# video_test.net
KiCad netlist of a schematic drawn in EAGLE
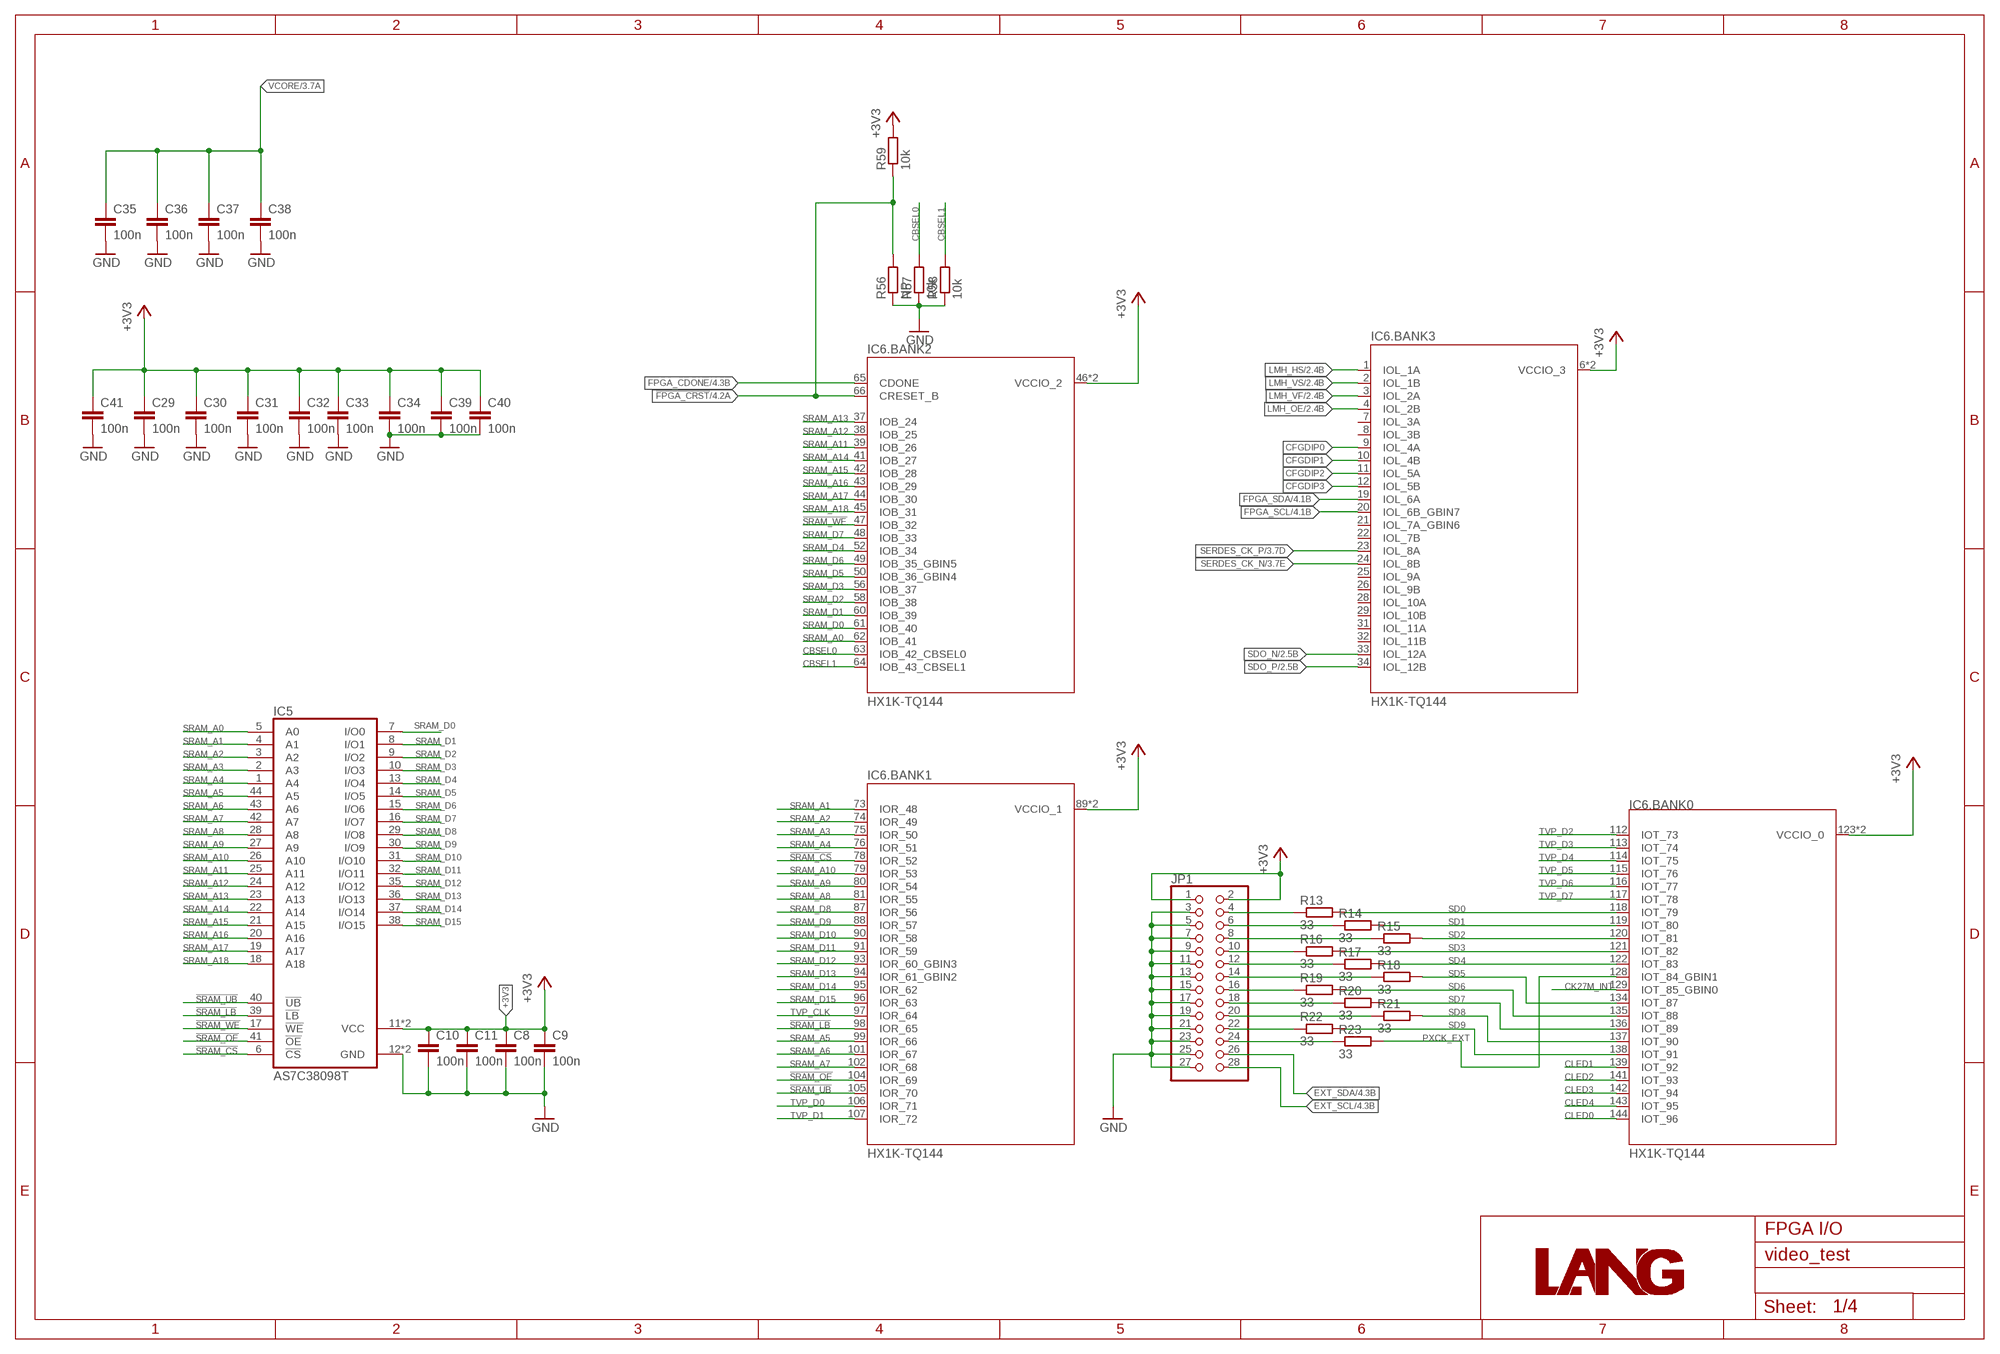
[diagram p0: schematic, sheet 1]
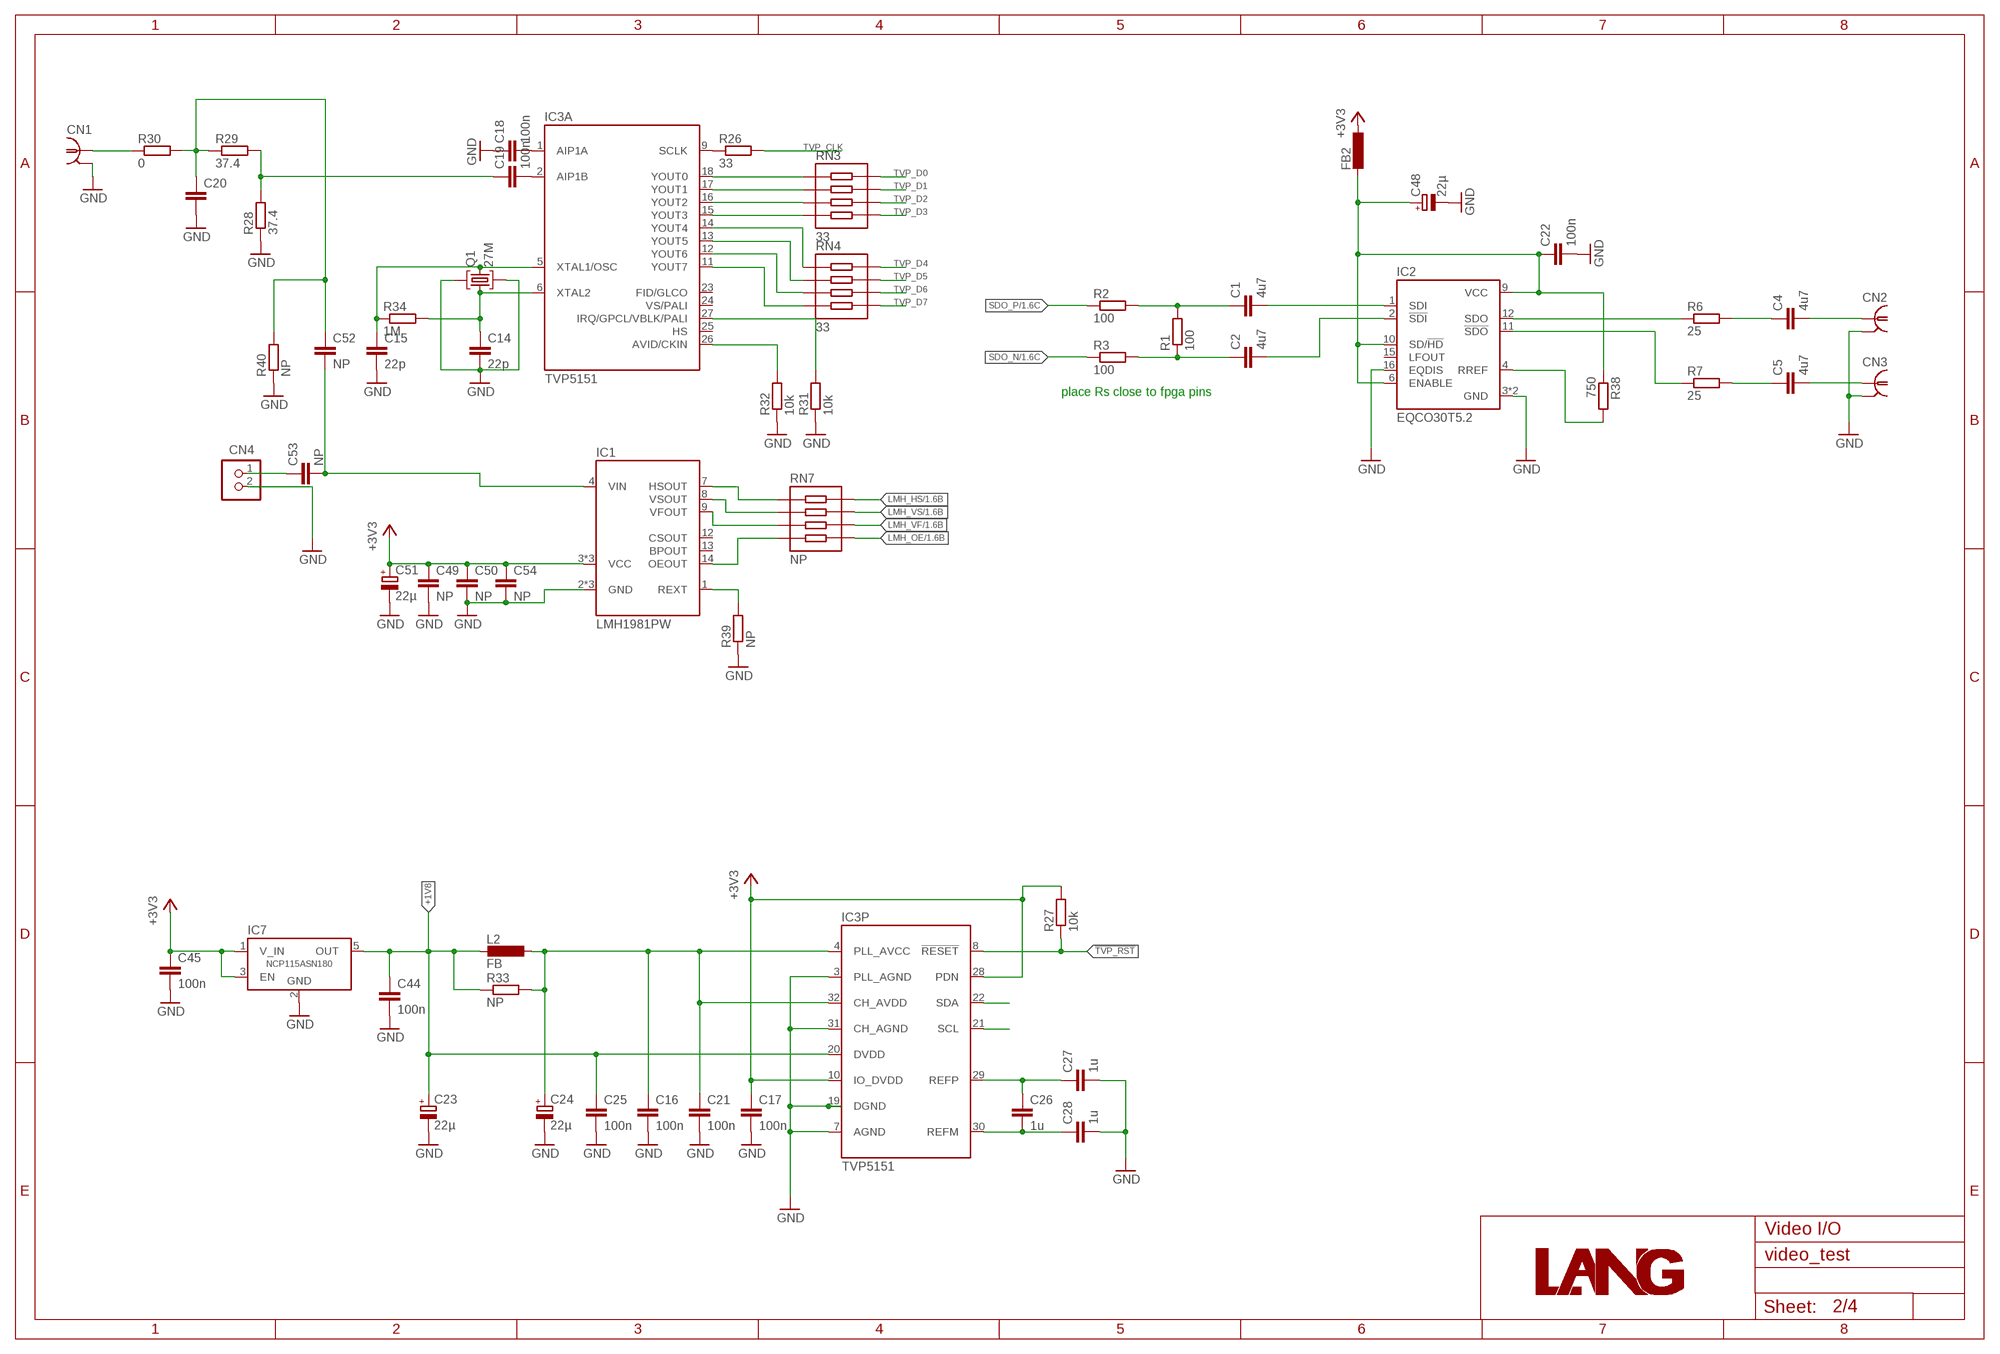
[diagram p1: schematic, sheet 2]
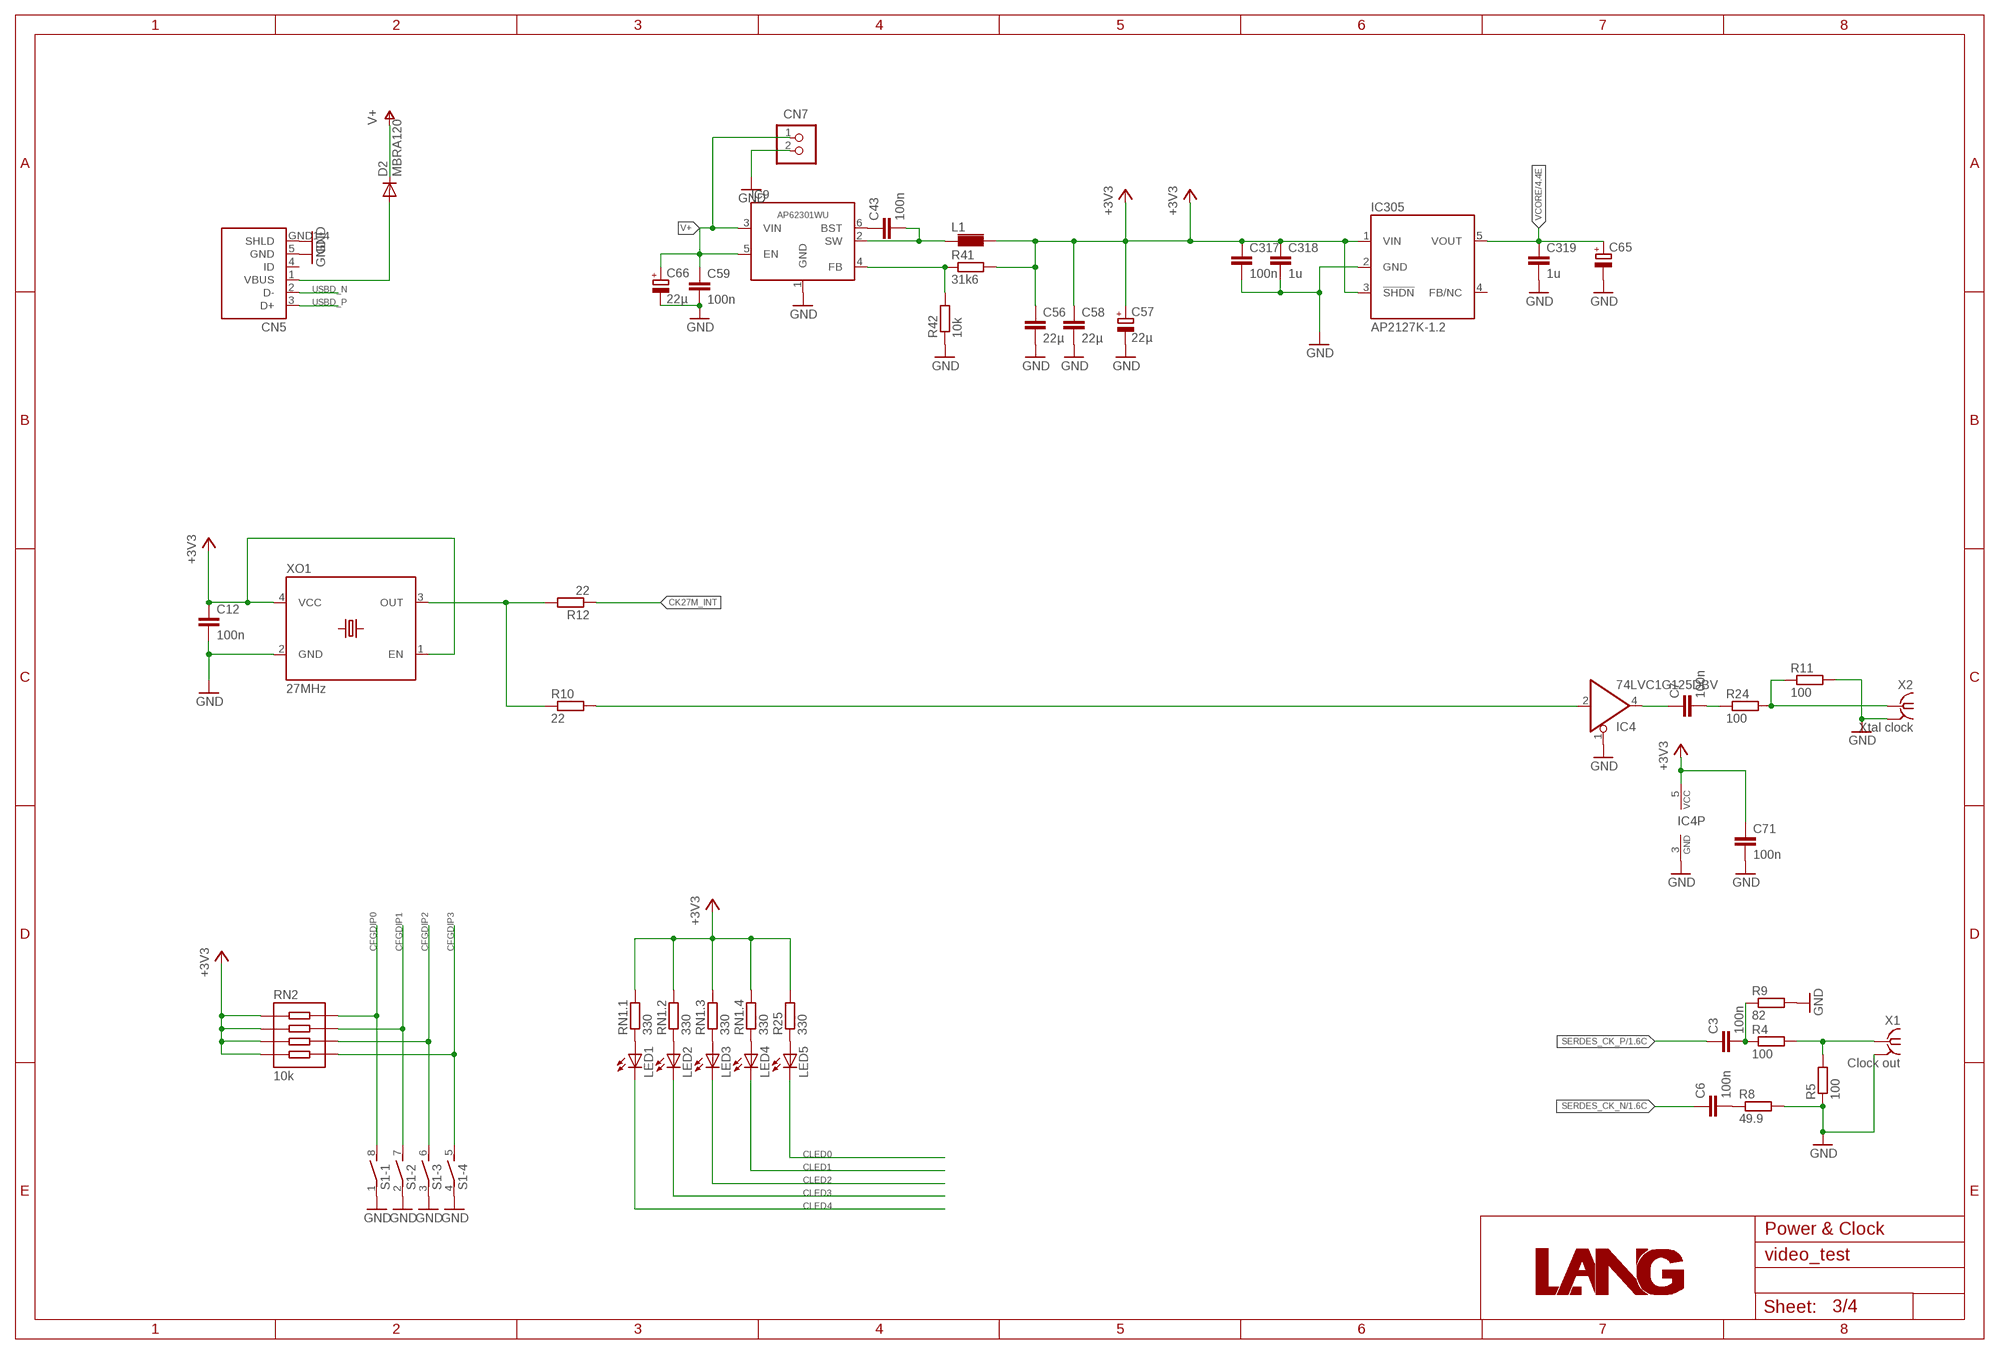
[diagram p2: schematic, sheet 3]
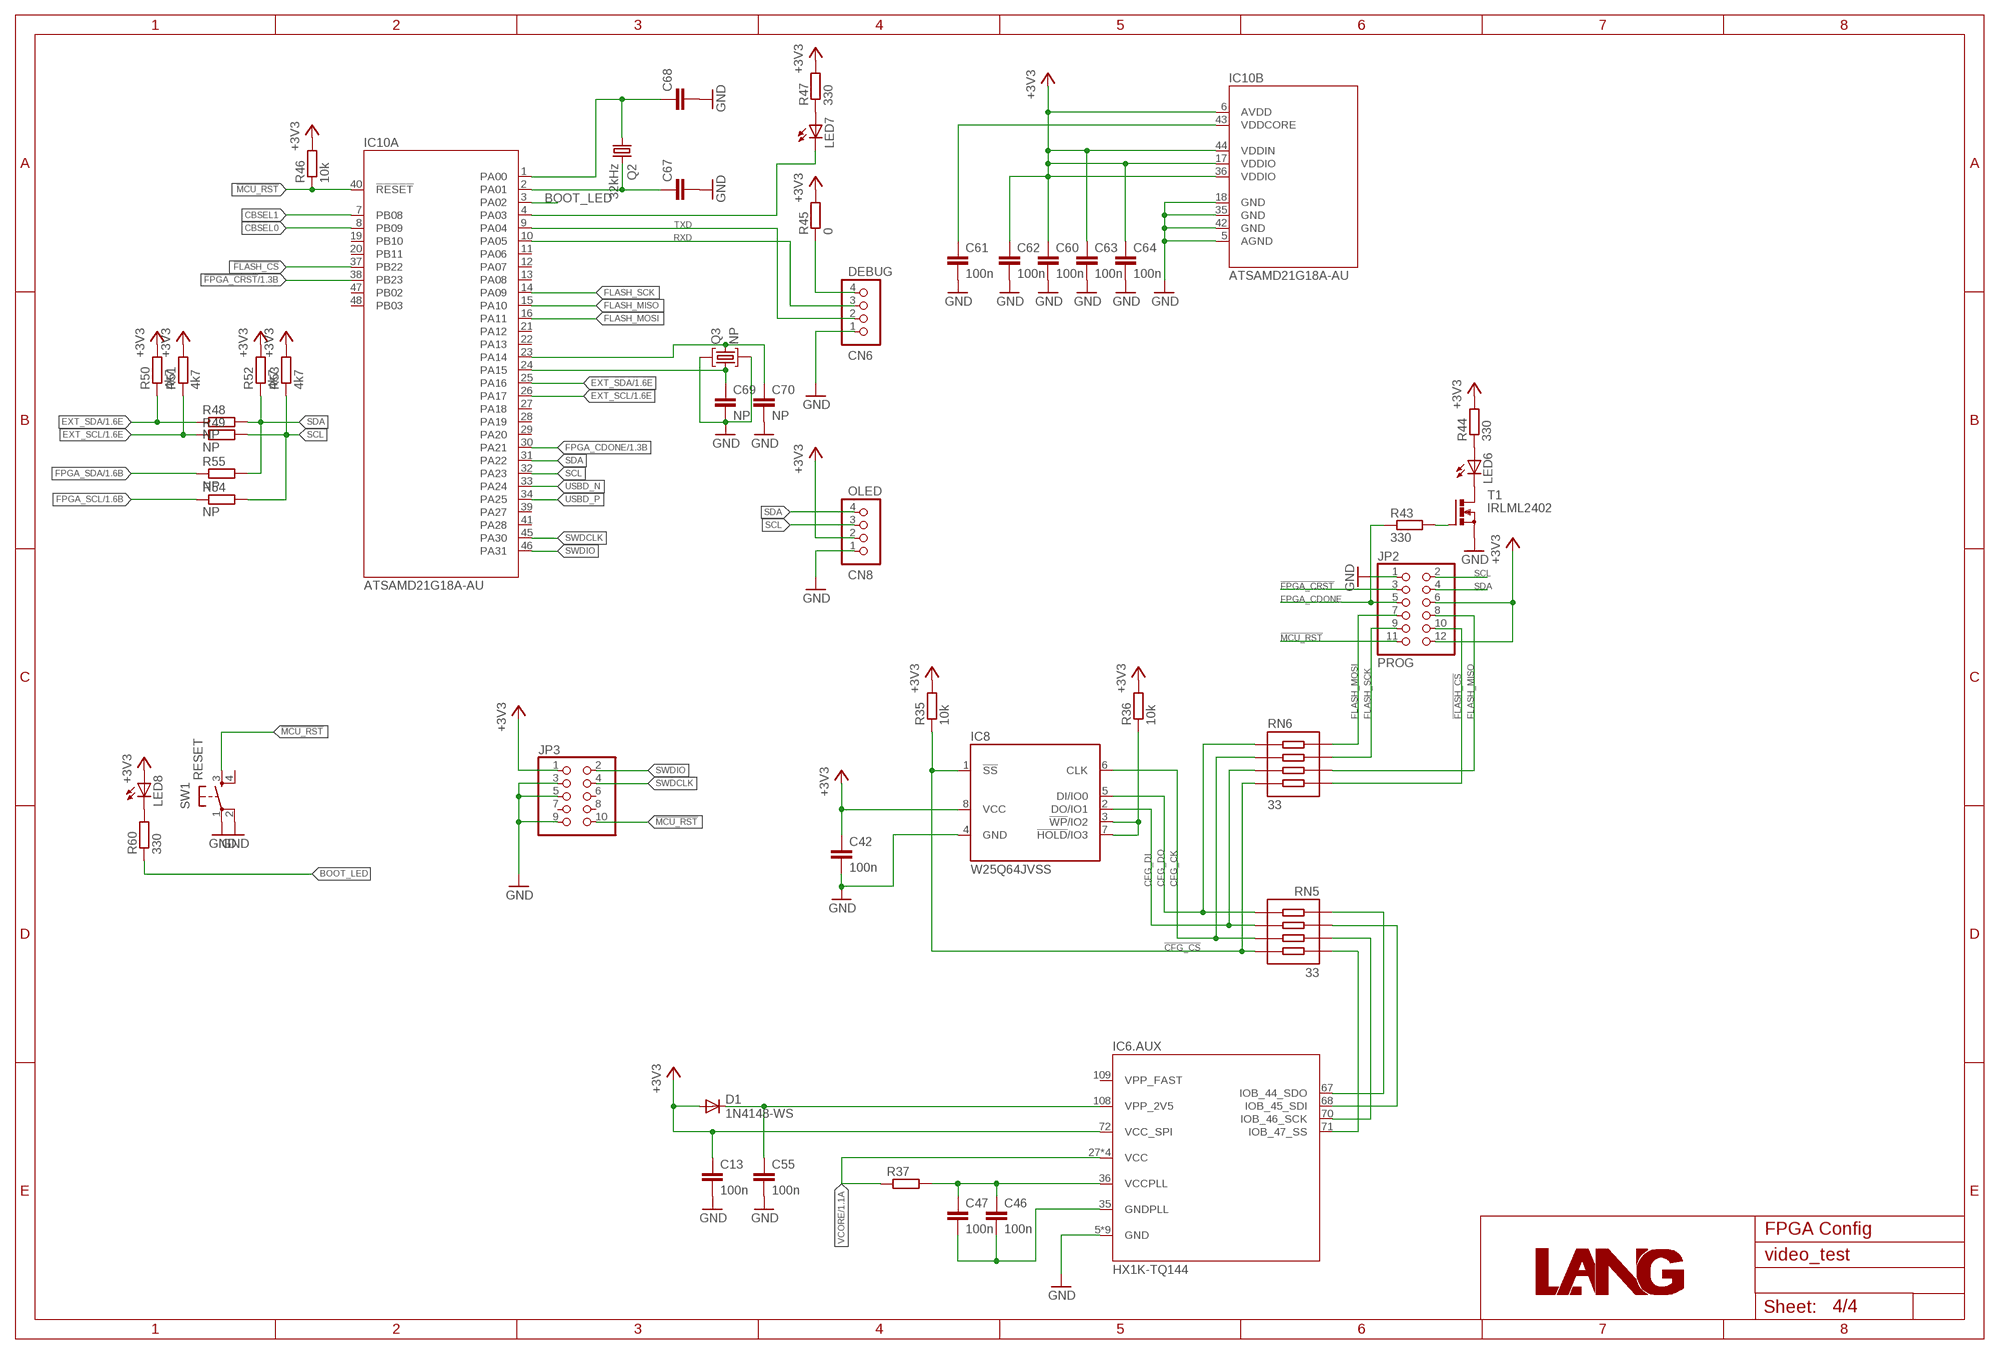
[diagram p3: schematic, sheet 4]

(export (version "E")
  (design (tool "Eeschema 10.0.6"))
  (components
    (comp (ref "C8")
      (value "100n")
      (footprint "eagle-import:C0603")
      (libsource (lib "eagle-import") (part "C-EUC0603"))
    )
    (comp (ref "C9")
      (value "100n")
      (footprint "eagle-import:C0603")
      (libsource (lib "eagle-import") (part "C-EUC0603"))
    )
    (comp (ref "C10")
      (value "100n")
      (footprint "eagle-import:C0402")
      (libsource (lib "eagle-import") (part "C-EUC0402"))
    )
    (comp (ref "C11")
      (value "100n")
      (footprint "eagle-import:C0402")
      (libsource (lib "eagle-import") (part "C-EUC0402"))
    )
    (comp (ref "C29")
      (value "100n")
      (footprint "eagle-import:C0402")
      (libsource (lib "eagle-import") (part "C-EUC0402"))
    )
    (comp (ref "C30")
      (value "100n")
      (footprint "eagle-import:C0402")
      (libsource (lib "eagle-import") (part "C-EUC0402"))
    )
    (comp (ref "C31")
      (value "100n")
      (footprint "eagle-import:C0402")
      (libsource (lib "eagle-import") (part "C-EUC0402"))
    )
    (comp (ref "C32")
      (value "100n")
      (footprint "eagle-import:C0402")
      (libsource (lib "eagle-import") (part "C-EUC0402"))
    )
    (comp (ref "C33")
      (value "100n")
      (footprint "eagle-import:C0402")
      (libsource (lib "eagle-import") (part "C-EUC0402"))
    )
    (comp (ref "C34")
      (value "100n")
      (footprint "eagle-import:C0402")
      (libsource (lib "eagle-import") (part "C-EUC0402"))
    )
    (comp (ref "C35")
      (value "100n")
      (footprint "eagle-import:C0402")
      (libsource (lib "eagle-import") (part "C-EUC0402"))
    )
    (comp (ref "C36")
      (value "100n")
      (footprint "eagle-import:C0402")
      (libsource (lib "eagle-import") (part "C-EUC0402"))
    )
    (comp (ref "C37")
      (value "100n")
      (footprint "eagle-import:C0402")
      (libsource (lib "eagle-import") (part "C-EUC0402"))
    )
    (comp (ref "C38")
      (value "100n")
      (footprint "eagle-import:C0402")
      (libsource (lib "eagle-import") (part "C-EUC0402"))
    )
    (comp (ref "C39")
      (value "100n")
      (footprint "eagle-import:C0402")
      (libsource (lib "eagle-import") (part "C-EUC0402"))
    )
    (comp (ref "C40")
      (value "100n")
      (footprint "eagle-import:C0402")
      (libsource (lib "eagle-import") (part "C-EUC0402"))
    )
    (comp (ref "C41")
      (value "100n")
      (footprint "eagle-import:C0402")
      (libsource (lib "eagle-import") (part "C-EUC0402"))
    )
    (comp (ref "IC5")
      (value "AS7C38098T")
      (footprint "eagle-import:TSOPII-Z44")
      (libsource (lib "eagle-import") (part "AS7C38098T"))
    )
    (comp (ref "IC6")
      (value "HX1K-TQ144")
      (footprint "eagle-import:QFP50P2200X2200X160-144N")
      (libsource (lib "eagle-import") (part "HX1K-TQ144"))
    )
    (comp (ref "JP1")
      (value "PINHD-2X14")
      (footprint "eagle-import:2X14")
      (libsource (lib "eagle-import") (part "PINHD-2X14"))
    )
    (comp (ref "R13")
      (value "33")
      (footprint "eagle-import:R0603")
      (libsource (lib "eagle-import") (part "R-EU_R0603"))
    )
    (comp (ref "R14")
      (value "33")
      (footprint "eagle-import:R0603")
      (libsource (lib "eagle-import") (part "R-EU_R0603"))
    )
    (comp (ref "R15")
      (value "33")
      (footprint "eagle-import:R0603")
      (libsource (lib "eagle-import") (part "R-EU_R0603"))
    )
    (comp (ref "R16")
      (value "33")
      (footprint "eagle-import:R0603")
      (libsource (lib "eagle-import") (part "R-EU_R0603"))
    )
    (comp (ref "R17")
      (value "33")
      (footprint "eagle-import:R0603")
      (libsource (lib "eagle-import") (part "R-EU_R0603"))
    )
    (comp (ref "R18")
      (value "33")
      (footprint "eagle-import:R0603")
      (libsource (lib "eagle-import") (part "R-EU_R0603"))
    )
    (comp (ref "R19")
      (value "33")
      (footprint "eagle-import:R0603")
      (libsource (lib "eagle-import") (part "R-EU_R0603"))
    )
    (comp (ref "R20")
      (value "33")
      (footprint "eagle-import:R0603")
      (libsource (lib "eagle-import") (part "R-EU_R0603"))
    )
    (comp (ref "R21")
      (value "33")
      (footprint "eagle-import:R0603")
      (libsource (lib "eagle-import") (part "R-EU_R0603"))
    )
    (comp (ref "R22")
      (value "33")
      (footprint "eagle-import:R0603")
      (libsource (lib "eagle-import") (part "R-EU_R0603"))
    )
    (comp (ref "R23")
      (value "33")
      (footprint "eagle-import:R0603")
      (libsource (lib "eagle-import") (part "R-EU_R0603"))
    )
    (comp (ref "R56")
      (value "NP")
      (footprint "eagle-import:R0402")
      (libsource (lib "eagle-import") (part "R-EU_R0402"))
    )
    (comp (ref "R57")
      (value "10k")
      (footprint "eagle-import:R0402")
      (libsource (lib "eagle-import") (part "R-EU_R0402"))
    )
    (comp (ref "R58")
      (value "10k")
      (footprint "eagle-import:R0402")
      (libsource (lib "eagle-import") (part "R-EU_R0402"))
    )
    (comp (ref "R59")
      (value "10k")
      (footprint "eagle-import:R0402")
      (libsource (lib "eagle-import") (part "R-EU_R0402"))
    )
    (comp (ref "C1")
      (value "4u7")
      (footprint "eagle-import:C0603")
      (libsource (lib "eagle-import") (part "C-EUC0603"))
    )
    (comp (ref "C2")
      (value "4u7")
      (footprint "eagle-import:C0603")
      (libsource (lib "eagle-import") (part "C-EUC0603"))
    )
    (comp (ref "C4")
      (value "4u7")
      (footprint "eagle-import:C0603")
      (libsource (lib "eagle-import") (part "C-EUC0603"))
    )
    (comp (ref "C5")
      (value "4u7")
      (footprint "eagle-import:C0603")
      (libsource (lib "eagle-import") (part "C-EUC0603"))
    )
    (comp (ref "C14")
      (value "22p")
      (footprint "eagle-import:C0603")
      (libsource (lib "eagle-import") (part "C-EUC0603"))
    )
    (comp (ref "C15")
      (value "22p")
      (footprint "eagle-import:C0603")
      (libsource (lib "eagle-import") (part "C-EUC0603"))
    )
    (comp (ref "C16")
      (value "100n")
      (footprint "eagle-import:C0402")
      (libsource (lib "eagle-import") (part "C-EUC0402"))
    )
    (comp (ref "C17")
      (value "100n")
      (footprint "eagle-import:C0402")
      (libsource (lib "eagle-import") (part "C-EUC0402"))
    )
    (comp (ref "C18")
      (value "100n")
      (footprint "eagle-import:C0402")
      (libsource (lib "eagle-import") (part "C-EUC0402"))
    )
    (comp (ref "C19")
      (value "100n")
      (footprint "eagle-import:C0402")
      (libsource (lib "eagle-import") (part "C-EUC0402"))
    )
    (comp (ref "C20")
      (value "C-EUC0603")
      (footprint "eagle-import:C0603")
      (libsource (lib "eagle-import") (part "C-EUC0603"))
    )
    (comp (ref "C21")
      (value "100n")
      (footprint "eagle-import:C0402")
      (libsource (lib "eagle-import") (part "C-EUC0402"))
    )
    (comp (ref "C22")
      (value "100n")
      (footprint "eagle-import:C0402")
      (libsource (lib "eagle-import") (part "C-EUC0402"))
    )
    (comp (ref "C23")
      (value "22µ")
      (footprint "eagle-import:B_3528-21R")
      (libsource (lib "eagle-import") (part "CPOL-EUB/3528-21R"))
    )
    (comp (ref "C24")
      (value "22µ")
      (footprint "eagle-import:B_3528-21R")
      (libsource (lib "eagle-import") (part "CPOL-EUB/3528-21R"))
    )
    (comp (ref "C25")
      (value "100n")
      (footprint "eagle-import:C0402")
      (libsource (lib "eagle-import") (part "C-EUC0402"))
    )
    (comp (ref "C26")
      (value "1u")
      (footprint "eagle-import:C0603")
      (libsource (lib "eagle-import") (part "C-EUC0603"))
    )
    (comp (ref "C27")
      (value "1u")
      (footprint "eagle-import:C0603")
      (libsource (lib "eagle-import") (part "C-EUC0603"))
    )
    (comp (ref "C28")
      (value "1u")
      (footprint "eagle-import:C0603")
      (libsource (lib "eagle-import") (part "C-EUC0603"))
    )
    (comp (ref "C44")
      (value "100n")
      (footprint "eagle-import:C0603")
      (libsource (lib "eagle-import") (part "C-EUC0603"))
    )
    (comp (ref "C45")
      (value "100n")
      (footprint "eagle-import:C0603")
      (libsource (lib "eagle-import") (part "C-EUC0603"))
    )
    (comp (ref "C48")
      (value "22µ")
      (footprint "eagle-import:PANASONIC_B")
      (libsource (lib "eagle-import") (part "CPOL-EUB"))
    )
    (comp (ref "C49")
      (value "NP")
      (footprint "eagle-import:C0402")
      (libsource (lib "eagle-import") (part "C-EUC0402"))
    )
    (comp (ref "C50")
      (value "NP")
      (footprint "eagle-import:C0402")
      (libsource (lib "eagle-import") (part "C-EUC0402"))
    )
    (comp (ref "C51")
      (value "22µ")
      (footprint "eagle-import:PANASONIC_B")
      (libsource (lib "eagle-import") (part "CPOL-EUB"))
    )
    (comp (ref "C52")
      (value "NP")
      (footprint "eagle-import:C0603")
      (libsource (lib "eagle-import") (part "C-EUC0603"))
    )
    (comp (ref "C53")
      (value "NP")
      (footprint "eagle-import:C0603")
      (libsource (lib "eagle-import") (part "C-EUC0603"))
    )
    (comp (ref "C54")
      (value "NP")
      (footprint "eagle-import:C0402")
      (libsource (lib "eagle-import") (part "C-EUC0402"))
    )
    (comp (ref "CN1")
      (value "BU-BNC-RA")
      (footprint "eagle-import:AMP_227161")
      (libsource (lib "eagle-import") (part "BU-BNC-RA"))
    )
    (comp (ref "CN2")
      (value "BU-BNC-RA")
      (footprint "eagle-import:AMP_227161")
      (libsource (lib "eagle-import") (part "BU-BNC-RA"))
    )
    (comp (ref "CN3")
      (value "BU-BNC-RA")
      (footprint "eagle-import:AMP_227161")
      (libsource (lib "eagle-import") (part "BU-BNC-RA"))
    )
    (comp (ref "CN4")
      (value "JST-XH2")
      (footprint "eagle-import:B2B-XH")
      (libsource (lib "eagle-import") (part "JST-XH2"))
    )
    (comp (ref "FB2")
      (value "L-EU_L0603")
      (footprint "eagle-import:R0603")
      (libsource (lib "eagle-import") (part "L-EU_L0603"))
    )
    (comp (ref "IC1")
      (value "LMH1981PW")
      (footprint "eagle-import:TSSOP14")
      (libsource (lib "eagle-import") (part "LMH1981PW"))
    )
    (comp (ref "IC2")
      (value "EQCO30T5.2")
      (footprint "eagle-import:QFN16_065")
      (libsource (lib "eagle-import") (part "EQCO30T5.2"))
    )
    (comp (ref "IC3")
      (value "TVP5151")
      (footprint "eagle-import:SPQFP32")
      (libsource (lib "eagle-import") (part "TVP5151"))
    )
    (comp (ref "IC7")
      (value "NCP115ASN180")
      (footprint "eagle-import:SOT23-5")
      (libsource (lib "eagle-import") (part "NCP115ASN180"))
    )
    (comp (ref "L2")
      (value "FB")
      (footprint "eagle-import:R0805")
      (libsource (lib "eagle-import") (part "L-EU_L0805"))
    )
    (comp (ref "Q1")
      (value "27M")
      (footprint "eagle-import:MT")
      (libsource (lib "eagle-import") (part "CRYSTAL_SHIELDEDMT"))
    )
    (comp (ref "R1")
      (value "100")
      (footprint "eagle-import:R0603")
      (libsource (lib "eagle-import") (part "R-EU_R0603"))
    )
    (comp (ref "R2")
      (value "100")
      (footprint "eagle-import:R0603")
      (libsource (lib "eagle-import") (part "R-EU_R0603"))
    )
    (comp (ref "R3")
      (value "100")
      (footprint "eagle-import:R0603")
      (libsource (lib "eagle-import") (part "R-EU_R0603"))
    )
    (comp (ref "R6")
      (value "25")
      (footprint "eagle-import:R0603")
      (libsource (lib "eagle-import") (part "R-EU_R0603"))
    )
    (comp (ref "R7")
      (value "25")
      (footprint "eagle-import:R0603")
      (libsource (lib "eagle-import") (part "R-EU_R0603"))
    )
    (comp (ref "R26")
      (value "33")
      (footprint "eagle-import:R0603")
      (libsource (lib "eagle-import") (part "R-EU_R0603"))
    )
    (comp (ref "R27")
      (value "10k")
      (footprint "eagle-import:R0402")
      (libsource (lib "eagle-import") (part "R-EU_R0402"))
    )
    (comp (ref "R28")
      (value "37.4")
      (footprint "eagle-import:R0603")
      (libsource (lib "eagle-import") (part "R-EU_R0603"))
    )
    (comp (ref "R29")
      (value "37.4")
      (footprint "eagle-import:R0603")
      (libsource (lib "eagle-import") (part "R-EU_R0603"))
    )
    (comp (ref "R30")
      (value "0")
      (footprint "eagle-import:R0603")
      (libsource (lib "eagle-import") (part "R-EU_R0603"))
    )
    (comp (ref "R31")
      (value "10k")
      (footprint "eagle-import:R0402")
      (libsource (lib "eagle-import") (part "R-EU_R0402"))
    )
    (comp (ref "R32")
      (value "10k")
      (footprint "eagle-import:R0402")
      (libsource (lib "eagle-import") (part "R-EU_R0402"))
    )
    (comp (ref "R33")
      (value "NP")
      (footprint "eagle-import:R0603")
      (libsource (lib "eagle-import") (part "R-EU_R0603"))
    )
    (comp (ref "R34")
      (value "1M")
      (footprint "eagle-import:R0603")
      (libsource (lib "eagle-import") (part "R-EU_R0603"))
    )
    (comp (ref "R38")
      (value "750")
      (footprint "eagle-import:R0603")
      (libsource (lib "eagle-import") (part "R-EU_R0603"))
    )
    (comp (ref "R39")
      (value "NP")
      (footprint "eagle-import:R0603")
      (libsource (lib "eagle-import") (part "R-EU_R0603"))
    )
    (comp (ref "R40")
      (value "NP")
      (footprint "eagle-import:R0603")
      (libsource (lib "eagle-import") (part "R-EU_R0603"))
    )
    (comp (ref "RN3")
      (value "33")
      (footprint "eagle-import:CTS742C083")
      (libsource (lib "eagle-import") (part "RN4-1-1206"))
    )
    (comp (ref "RN4")
      (value "33")
      (footprint "eagle-import:CTS742C083")
      (libsource (lib "eagle-import") (part "RN4-1-1206"))
    )
    (comp (ref "RN7")
      (value "NP")
      (footprint "eagle-import:CTS742C083")
      (libsource (lib "eagle-import") (part "RN4-1-1206"))
    )
    (comp (ref "C13")
      (value "100n")
      (footprint "eagle-import:C0402")
      (libsource (lib "eagle-import") (part "C-EUC0402"))
    )
    (comp (ref "C42")
      (value "100n")
      (footprint "eagle-import:C0603")
      (libsource (lib "eagle-import") (part "C-EUC0603"))
    )
    (comp (ref "C46")
      (value "100n")
      (footprint "eagle-import:C0402")
      (libsource (lib "eagle-import") (part "C-EUC0402"))
    )
    (comp (ref "C47")
      (value "100n")
      (footprint "eagle-import:C0603")
      (libsource (lib "eagle-import") (part "C-EUC0603"))
    )
    (comp (ref "C55")
      (value "100n")
      (footprint "eagle-import:C0402")
      (libsource (lib "eagle-import") (part "C-EUC0402"))
    )
    (comp (ref "C60")
      (value "100n")
      (footprint "eagle-import:C0402")
      (libsource (lib "eagle-import") (part "C-EUC0402"))
    )
    (comp (ref "C61")
      (value "100n")
      (footprint "eagle-import:C0402")
      (libsource (lib "eagle-import") (part "C-EUC0402"))
    )
    (comp (ref "C62")
      (value "100n")
      (footprint "eagle-import:C0402")
      (libsource (lib "eagle-import") (part "C-EUC0402"))
    )
    (comp (ref "C63")
      (value "100n")
      (footprint "eagle-import:C0402")
      (libsource (lib "eagle-import") (part "C-EUC0402"))
    )
    (comp (ref "C64")
      (value "100n")
      (footprint "eagle-import:C0402")
      (libsource (lib "eagle-import") (part "C-EUC0402"))
    )
    (comp (ref "C67")
      (value "C-EUC0402")
      (footprint "eagle-import:C0402")
      (libsource (lib "eagle-import") (part "C-EUC0402"))
    )
    (comp (ref "C68")
      (value "C-EUC0402")
      (footprint "eagle-import:C0402")
      (libsource (lib "eagle-import") (part "C-EUC0402"))
    )
    (comp (ref "C69")
      (value "NP")
      (footprint "eagle-import:C0603")
      (libsource (lib "eagle-import") (part "C-EUC0603"))
    )
    (comp (ref "C70")
      (value "NP")
      (footprint "eagle-import:C0603")
      (libsource (lib "eagle-import") (part "C-EUC0603"))
    )
    (comp (ref "CN6")
      (value "DEBUG")
      (footprint "eagle-import:SL-254-RH-4")
      (libsource (lib "eagle-import") (part "PINHD-1X4-RH"))
    )
    (comp (ref "CN8")
      (value "OLED")
      (footprint "eagle-import:SL-254-RH-4")
      (libsource (lib "eagle-import") (part "PINHD-1X4-RH"))
    )
    (comp (ref "D1")
      (value "1N4148-WS")
      (footprint "eagle-import:SOD323")
      (libsource (lib "eagle-import") (part "1N4148-WS"))
    )
    (comp (ref "IC8")
      (value "W25Q64JVSS")
      (footprint "eagle-import:SO-08M")
      (libsource (lib "eagle-import") (part "W25QJVSS64"))
    )
    (comp (ref "IC10")
      (value "ATSAMD21G18A-AU")
      (footprint "eagle-import:TQFP48_7X7MC_MCH")
      (fields (field (name "COPYRIGHT") "Copyright (C) 2018 Accelerated Designs. All rights reserved"))
      (libsource (lib "eagle-import") (part "ATSAMD21G18A-AU"))
    )
    (comp (ref "JP2")
      (value "PROG")
      (footprint "eagle-import:2X06")
      (libsource (lib "eagle-import") (part "PINHD-2X6"))
    )
    (comp (ref "JP3")
      (value "PINHD-2X5-127")
      (footprint "eagle-import:SL127-2X5")
      (libsource (lib "eagle-import") (part "PINHD-2X5-127"))
    )
    (comp (ref "LED6")
      (value "LEDCHIP-LED0603")
      (footprint "eagle-import:CHIP-LED0603")
      (libsource (lib "eagle-import") (part "LEDCHIP-LED0603"))
    )
    (comp (ref "LED7")
      (value "LEDCHIP-LED0603")
      (footprint "eagle-import:CHIP-LED0603")
      (libsource (lib "eagle-import") (part "LEDCHIP-LED0603"))
    )
    (comp (ref "LED8")
      (value "LEDCHIP-LED0603")
      (footprint "eagle-import:CHIP-LED0603")
      (libsource (lib "eagle-import") (part "LEDCHIP-LED0603"))
    )
    (comp (ref "Q2")
      (value "32kHz")
      (footprint "eagle-import:IQXC-25")
      (libsource (lib "eagle-import") (part "CRYSTAL-IQXC-25"))
    )
    (comp (ref "Q3")
      (value "NP")
      (footprint "eagle-import:MT")
      (libsource (lib "eagle-import") (part "CRYSTAL_SHIELDEDMT"))
    )
    (comp (ref "R35")
      (value "10k")
      (footprint "eagle-import:R0603")
      (libsource (lib "eagle-import") (part "R-EU_R0603"))
    )
    (comp (ref "R36")
      (value "10k")
      (footprint "eagle-import:R0603")
      (libsource (lib "eagle-import") (part "R-EU_R0603"))
    )
    (comp (ref "R37")
      (value "R-EU_R0603")
      (footprint "eagle-import:R0603")
      (libsource (lib "eagle-import") (part "R-EU_R0603"))
    )
    (comp (ref "R43")
      (value "330")
      (footprint "eagle-import:R0603")
      (libsource (lib "eagle-import") (part "R-EU_R0603"))
    )
    (comp (ref "R44")
      (value "330")
      (footprint "eagle-import:R0603")
      (libsource (lib "eagle-import") (part "R-EU_R0603"))
    )
    (comp (ref "R45")
      (value "0")
      (footprint "eagle-import:R0603")
      (libsource (lib "eagle-import") (part "R-EU_R0603"))
    )
    (comp (ref "R46")
      (value "10k")
      (footprint "eagle-import:R0603")
      (libsource (lib "eagle-import") (part "R-EU_R0603"))
    )
    (comp (ref "R47")
      (value "330")
      (footprint "eagle-import:R0603")
      (libsource (lib "eagle-import") (part "R-EU_R0603"))
    )
    (comp (ref "R48")
      (value "NP")
      (footprint "eagle-import:R0603")
      (libsource (lib "eagle-import") (part "R-EU_R0603"))
    )
    (comp (ref "R49")
      (value "NP")
      (footprint "eagle-import:R0603")
      (libsource (lib "eagle-import") (part "R-EU_R0603"))
    )
    (comp (ref "R50")
      (value "4k7")
      (footprint "eagle-import:R0603")
      (libsource (lib "eagle-import") (part "R-EU_R0603"))
    )
    (comp (ref "R51")
      (value "4k7")
      (footprint "eagle-import:R0603")
      (libsource (lib "eagle-import") (part "R-EU_R0603"))
    )
    (comp (ref "R52")
      (value "4k7")
      (footprint "eagle-import:R0603")
      (libsource (lib "eagle-import") (part "R-EU_R0603"))
    )
    (comp (ref "R53")
      (value "4k7")
      (footprint "eagle-import:R0603")
      (libsource (lib "eagle-import") (part "R-EU_R0603"))
    )
    (comp (ref "R54")
      (value "NP")
      (footprint "eagle-import:R0402")
      (libsource (lib "eagle-import") (part "R-EU_R0402"))
    )
    (comp (ref "R55")
      (value "NP")
      (footprint "eagle-import:R0402")
      (libsource (lib "eagle-import") (part "R-EU_R0402"))
    )
    (comp (ref "R60")
      (value "330")
      (footprint "eagle-import:R0603")
      (libsource (lib "eagle-import") (part "R-EU_R0603"))
    )
    (comp (ref "RN5")
      (value "33")
      (footprint "eagle-import:CTS742C083")
      (libsource (lib "eagle-import") (part "RN4-1-1206"))
    )
    (comp (ref "RN6")
      (value "33")
      (footprint "eagle-import:CTS742C083")
      (libsource (lib "eagle-import") (part "RN4-1-1206"))
    )
    (comp (ref "SW1")
      (value "RESET")
      (footprint "eagle-import:PTS526")
      (libsource (lib "eagle-import") (part "PTS526-S15M"))
    )
    (comp (ref "T1")
      (value "IRLML2402")
      (footprint "eagle-import:SOT23")
      (libsource (lib "eagle-import") (part "IRLML2402"))
    )
    (comp (ref "C3")
      (value "100n")
      (footprint "eagle-import:C0603")
      (libsource (lib "eagle-import") (part "C-EUC0603"))
    )
    (comp (ref "C6")
      (value "100n")
      (footprint "eagle-import:C0603")
      (libsource (lib "eagle-import") (part "C-EUC0603"))
    )
    (comp (ref "C7")
      (value "100n")
      (footprint "eagle-import:C0603")
      (libsource (lib "eagle-import") (part "C-EUC0603"))
    )
    (comp (ref "C12")
      (value "100n")
      (footprint "eagle-import:C0603")
      (libsource (lib "eagle-import") (part "C-EUC0603"))
    )
    (comp (ref "C43")
      (value "100n")
      (footprint "eagle-import:C0603")
      (libsource (lib "eagle-import") (part "C-EUC0603"))
    )
    (comp (ref "C56")
      (value "22µ")
      (footprint "eagle-import:C0805")
      (libsource (lib "eagle-import") (part "C-EUC0805"))
    )
    (comp (ref "C57")
      (value "22µ")
      (footprint "eagle-import:PANASONIC_B")
      (libsource (lib "eagle-import") (part "CPOL-EUB"))
    )
    (comp (ref "C58")
      (value "22µ")
      (footprint "eagle-import:C0805")
      (libsource (lib "eagle-import") (part "C-EUC0805"))
    )
    (comp (ref "C59")
      (value "100n")
      (footprint "eagle-import:C0603")
      (libsource (lib "eagle-import") (part "C-EUC0603"))
    )
    (comp (ref "C65")
      (value "CPOL-EUB/3528-21R")
      (footprint "eagle-import:B_3528-21R")
      (libsource (lib "eagle-import") (part "CPOL-EUB/3528-21R"))
    )
    (comp (ref "C66")
      (value "22µ")
      (footprint "eagle-import:PANASONIC_C")
      (libsource (lib "eagle-import") (part "CPOL-EUC"))
    )
    (comp (ref "C71")
      (value "100n")
      (footprint "eagle-import:C0603")
      (libsource (lib "eagle-import") (part "C-EUC0603"))
    )
    (comp (ref "C317")
      (value "100n")
      (footprint "eagle-import:C0603")
      (libsource (lib "eagle-import") (part "C-EUC0603"))
    )
    (comp (ref "C318")
      (value "1u")
      (footprint "eagle-import:C0603")
      (libsource (lib "eagle-import") (part "C-EUC0603"))
    )
    (comp (ref "C319")
      (value "1u")
      (footprint "eagle-import:C0603")
      (libsource (lib "eagle-import") (part "C-EUC0603"))
    )
    (comp (ref "CN5")
      (value "USB-UJ2-MIBH-G")
      (footprint "eagle-import:UJ2-MIBH-G-SMT")
      (libsource (lib "eagle-import") (part "USB-UJ2-MIBH-G"))
    )
    (comp (ref "CN7")
      (value "JST-XH2")
      (footprint "eagle-import:B2B-XH")
      (libsource (lib "eagle-import") (part "JST-XH2"))
    )
    (comp (ref "D2")
      (value "MBRA120")
      (footprint "eagle-import:SMA")
      (libsource (lib "eagle-import") (part "MBRA120"))
    )
    (comp (ref "IC4")
      (value "74LVC1G125DBV")
      (footprint "eagle-import:SOT23-5")
      (libsource (lib "eagle-import") (part "741G125DBVLVC"))
    )
    (comp (ref "IC9")
      (value "AP62301WU")
      (footprint "eagle-import:SOT23-6L")
      (libsource (lib "eagle-import") (part "AP62301WU"))
    )
    (comp (ref "IC305")
      (value "AP2127K-1.2")
      (footprint "eagle-import:SOT23-5")
      (libsource (lib "eagle-import") (part "AP2127K-1.2"))
    )
    (comp (ref "L1")
      (value "L-TYA4020")
      (footprint "eagle-import:TYA4020")
      (libsource (lib "eagle-import") (part "L-TYA4020"))
    )
    (comp (ref "LED1")
      (value "LEDCHIP-LED0603")
      (footprint "eagle-import:CHIP-LED0603")
      (libsource (lib "eagle-import") (part "LEDCHIP-LED0603"))
    )
    (comp (ref "LED2")
      (value "LEDCHIP-LED0603")
      (footprint "eagle-import:CHIP-LED0603")
      (libsource (lib "eagle-import") (part "LEDCHIP-LED0603"))
    )
    (comp (ref "LED3")
      (value "LEDCHIP-LED0603")
      (footprint "eagle-import:CHIP-LED0603")
      (libsource (lib "eagle-import") (part "LEDCHIP-LED0603"))
    )
    (comp (ref "LED4")
      (value "LEDCHIP-LED0603")
      (footprint "eagle-import:CHIP-LED0603")
      (libsource (lib "eagle-import") (part "LEDCHIP-LED0603"))
    )
    (comp (ref "LED5")
      (value "LEDCHIP-LED0603")
      (footprint "eagle-import:CHIP-LED0603")
      (libsource (lib "eagle-import") (part "LEDCHIP-LED0603"))
    )
    (comp (ref "R4")
      (value "100")
      (footprint "eagle-import:R0603")
      (libsource (lib "eagle-import") (part "R-EU_R0603"))
    )
    (comp (ref "R5")
      (value "100")
      (footprint "eagle-import:R0603")
      (libsource (lib "eagle-import") (part "R-EU_R0603"))
    )
    (comp (ref "R8")
      (value "49.9")
      (footprint "eagle-import:R0603")
      (libsource (lib "eagle-import") (part "R-EU_R0603"))
    )
    (comp (ref "R9")
      (value "82")
      (footprint "eagle-import:R0603")
      (libsource (lib "eagle-import") (part "R-EU_R0603"))
    )
    (comp (ref "R10")
      (value "22")
      (footprint "eagle-import:R0603")
      (libsource (lib "eagle-import") (part "R-EU_R0603"))
    )
    (comp (ref "R11")
      (value "100")
      (footprint "eagle-import:R0603")
      (libsource (lib "eagle-import") (part "R-EU_R0603"))
    )
    (comp (ref "R12")
      (value "22")
      (footprint "eagle-import:R0603")
      (libsource (lib "eagle-import") (part "R-EU_R0603"))
    )
    (comp (ref "R24")
      (value "100")
      (footprint "eagle-import:R0603")
      (libsource (lib "eagle-import") (part "R-EU_R0603"))
    )
    (comp (ref "R25")
      (value "330")
      (footprint "eagle-import:R0603")
      (libsource (lib "eagle-import") (part "R-EU_R0603"))
    )
    (comp (ref "R41")
      (value "31k6")
      (footprint "eagle-import:R0603")
      (libsource (lib "eagle-import") (part "R-EU_R0603"))
    )
    (comp (ref "R42")
      (value "10k")
      (footprint "eagle-import:R0603")
      (libsource (lib "eagle-import") (part "R-EU_R0603"))
    )
    (comp (ref "RN1")
      (value "330")
      (footprint "eagle-import:CTS742C083")
      (libsource (lib "eagle-import") (part "RN4-1206"))
    )
    (comp (ref "RN2")
      (value "10k")
      (footprint "eagle-import:CTS742C083")
      (libsource (lib "eagle-import") (part "RN4-1-1206"))
    )
    (comp (ref "S1")
      (value "DIP04S")
      (footprint "eagle-import:DIP04S")
      (libsource (lib "eagle-import") (part "DIP04S"))
    )
    (comp (ref "X1")
      (value "Clock out")
      (footprint "eagle-import:BU-SMA-V")
      (libsource (lib "eagle-import") (part "BU-SMA-V"))
    )
    (comp (ref "X2")
      (value "Xtal clock")
      (footprint "eagle-import:BU-SMA-V")
      (libsource (lib "eagle-import") (part "BU-SMA-V"))
    )
    (comp (ref "XO1")
      (value "27MHz")
      (footprint "eagle-import:ECS-2333")
      (libsource (lib "eagle-import") (part "XO-SMD"))
    )
  )
  (nets
    (net (code "1") (name "+1V8") (class "Default")
      (node (ref "C23") (pin "+") (pinfunction "+_+") (pintype "passive"))
      (node (ref "C25") (pin "1") (pinfunction "1_1") (pintype "passive"))
      (node (ref "C44") (pin "1") (pinfunction "1_1") (pintype "passive"))
      (node (ref "IC3") (pin "20") (pinfunction "DVDD_20") (pintype "power_in"))
      (node (ref "IC7") (pin "5") (pinfunction "OUT_5") (pintype "output"))
      (node (ref "L2") (pin "2") (pinfunction "2_2") (pintype "passive"))
      (node (ref "R33") (pin "1") (pinfunction "1_1") (pintype "passive"))
    )
    (net (code "2") (name "+3V3") (class "Default")
      (node (ref "C10") (pin "1") (pinfunction "1_1") (pintype "passive"))
      (node (ref "C11") (pin "1") (pinfunction "1_1") (pintype "passive"))
      (node (ref "C12") (pin "1") (pinfunction "1_1") (pintype "passive"))
      (node (ref "C13") (pin "1") (pinfunction "1_1") (pintype "passive"))
      (node (ref "C17") (pin "1") (pinfunction "1_1") (pintype "passive"))
      (node (ref "C29") (pin "1") (pinfunction "1_1") (pintype "passive"))
      (node (ref "C30") (pin "1") (pinfunction "1_1") (pintype "passive"))
      (node (ref "C31") (pin "1") (pinfunction "1_1") (pintype "passive"))
      (node (ref "C317") (pin "1") (pinfunction "1_1") (pintype "passive"))
      (node (ref "C318") (pin "1") (pinfunction "1_1") (pintype "passive"))
      (node (ref "C32") (pin "1") (pinfunction "1_1") (pintype "passive"))
      (node (ref "C33") (pin "1") (pinfunction "1_1") (pintype "passive"))
      (node (ref "C34") (pin "1") (pinfunction "1_1") (pintype "passive"))
      (node (ref "C39") (pin "1") (pinfunction "1_1") (pintype "passive"))
      (node (ref "C40") (pin "1") (pinfunction "1_1") (pintype "passive"))
      (node (ref "C41") (pin "1") (pinfunction "1_1") (pintype "passive"))
      (node (ref "C42") (pin "1") (pinfunction "1_1") (pintype "passive"))
      (node (ref "C45") (pin "1") (pinfunction "1_1") (pintype "passive"))
      (node (ref "C49") (pin "1") (pinfunction "1_1") (pintype "passive"))
      (node (ref "C50") (pin "1") (pinfunction "1_1") (pintype "passive"))
      (node (ref "C51") (pin "+") (pinfunction "+_+") (pintype "passive"))
      (node (ref "C54") (pin "1") (pinfunction "1_1") (pintype "passive"))
      (node (ref "C56") (pin "1") (pinfunction "1_1") (pintype "passive"))
      (node (ref "C57") (pin "+") (pinfunction "+_+") (pintype "passive"))
      (node (ref "C58") (pin "1") (pinfunction "1_1") (pintype "passive"))
      (node (ref "C60") (pin "1") (pinfunction "1_1") (pintype "passive"))
      (node (ref "C62") (pin "1") (pinfunction "1_1") (pintype "passive"))
      (node (ref "C63") (pin "1") (pinfunction "1_1") (pintype "passive"))
      (node (ref "C64") (pin "1") (pinfunction "1_1") (pintype "passive"))
      (node (ref "C71") (pin "1") (pinfunction "1_1") (pintype "passive"))
      (node (ref "C8") (pin "1") (pinfunction "1_1") (pintype "passive"))
      (node (ref "C9") (pin "1") (pinfunction "1_1") (pintype "passive"))
      (node (ref "CN8") (pin "2") (pinfunction "2_2") (pintype "bidirectional"))
      (node (ref "D1") (pin "A") (pinfunction "A_A") (pintype "passive"))
      (node (ref "FB2") (pin "1") (pinfunction "1_1") (pintype "passive"))
      (node (ref "IC1") (pin "11") (pinfunction "VCC_11") (pintype "power_in"))
      (node (ref "IC1") (pin "3") (pinfunction "VCC_3") (pintype "power_in"))
      (node (ref "IC1") (pin "6") (pinfunction "VCC_6") (pintype "power_in"))
      (node (ref "IC10") (pin "17") (pinfunction "VDDIO_17") (pintype "power_in"))
      (node (ref "IC10") (pin "36") (pinfunction "VDDIO_36") (pintype "power_in"))
      (node (ref "IC10") (pin "44") (pinfunction "VDDIN_44") (pintype "power_in"))
      (node (ref "IC10") (pin "6") (pinfunction "AVDD_6") (pintype "power_in"))
      (node (ref "IC3") (pin "10") (pinfunction "IO_DVDD_10") (pintype "power_in"))
      (node (ref "IC3") (pin "28") (pinfunction "PDN_28") (pintype "output"))
      (node (ref "IC305") (pin "1") (pinfunction "VIN_1") (pintype "power_in"))
      (node (ref "IC305") (pin "3") (pinfunction "~{SHDN}_3") (pintype "passive"))
      (node (ref "IC4") (pin "5") (pinfunction "VCC_5") (pintype "power_in"))
      (node (ref "IC5") (pin "11") (pinfunction "VCC_11") (pintype "power_in"))
      (node (ref "IC5") (pin "33") (pinfunction "VCC_33") (pintype "power_in"))
      (node (ref "IC6") (pin "100") (pinfunction "VCCIO_1_100") (pintype "bidirectional"))
      (node (ref "IC6") (pin "123") (pinfunction "VCCIO_0_123") (pintype "bidirectional"))
      (node (ref "IC6") (pin "133") (pinfunction "VCCIO_0_133") (pintype "bidirectional"))
      (node (ref "IC6") (pin "30") (pinfunction "VCCIO_3_30") (pintype "bidirectional"))
      (node (ref "IC6") (pin "46") (pinfunction "VCCIO_2_46") (pintype "bidirectional"))
      (node (ref "IC6") (pin "57") (pinfunction "VCCIO_2_57") (pintype "bidirectional"))
      (node (ref "IC6") (pin "6") (pinfunction "VCCIO_3_6") (pintype "bidirectional"))
      (node (ref "IC6") (pin "72") (pinfunction "VCC_SPI_72") (pintype "power_in"))
      (node (ref "IC6") (pin "89") (pinfunction "VCCIO_1_89") (pintype "bidirectional"))
      (node (ref "IC7") (pin "1") (pinfunction "V_IN_1") (pintype "power_in"))
      (node (ref "IC7") (pin "3") (pinfunction "EN_3") (pintype "input"))
      (node (ref "IC8") (pin "8") (pinfunction "VCC_8") (pintype "bidirectional"))
      (node (ref "JP1") (pin "1") (pinfunction "1_1") (pintype "passive"))
      (node (ref "JP1") (pin "2") (pinfunction "2_2") (pintype "passive"))
      (node (ref "JP2") (pin "12") (pinfunction "12_12") (pintype "passive"))
      (node (ref "JP2") (pin "6") (pinfunction "6_6") (pintype "passive"))
      (node (ref "JP3") (pin "1") (pinfunction "1_1") (pintype "passive"))
      (node (ref "L1") (pin "2") (pinfunction "P$2_2") (pintype "passive"))
      (node (ref "LED8") (pin "A") (pinfunction "A_A") (pintype "passive"))
      (node (ref "R25") (pin "2") (pinfunction "2_2") (pintype "passive"))
      (node (ref "R27") (pin "2") (pinfunction "2_2") (pintype "passive"))
      (node (ref "R35") (pin "2") (pinfunction "2_2") (pintype "passive"))
      (node (ref "R36") (pin "2") (pinfunction "2_2") (pintype "passive"))
      (node (ref "R41") (pin "2") (pinfunction "2_2") (pintype "passive"))
      (node (ref "R44") (pin "2") (pinfunction "2_2") (pintype "passive"))
      (node (ref "R45") (pin "2") (pinfunction "2_2") (pintype "passive"))
      (node (ref "R46") (pin "2") (pinfunction "2_2") (pintype "passive"))
      (node (ref "R47") (pin "2") (pinfunction "2_2") (pintype "passive"))
      (node (ref "R50") (pin "2") (pinfunction "2_2") (pintype "passive"))
      (node (ref "R51") (pin "2") (pinfunction "2_2") (pintype "passive"))
      (node (ref "R52") (pin "2") (pinfunction "2_2") (pintype "passive"))
      (node (ref "R53") (pin "2") (pinfunction "2_2") (pintype "passive"))
      (node (ref "R59") (pin "2") (pinfunction "2_2") (pintype "passive"))
      (node (ref "RN1") (pin "5") (pinfunction "2_5") (pintype "passive"))
      (node (ref "RN1") (pin "6") (pinfunction "2_6") (pintype "passive"))
      (node (ref "RN1") (pin "7") (pinfunction "2_7") (pintype "passive"))
      (node (ref "RN1") (pin "8") (pinfunction "2_8") (pintype "passive"))
      (node (ref "RN2") (pin "1") (pinfunction "A1_1") (pintype "passive"))
      (node (ref "RN2") (pin "2") (pinfunction "A2_2") (pintype "passive"))
      (node (ref "RN2") (pin "3") (pinfunction "A3_3") (pintype "passive"))
      (node (ref "RN2") (pin "4") (pinfunction "A4_4") (pintype "passive"))
      (node (ref "XO1") (pin "1") (pinfunction "EN_1") (pintype "input"))
      (node (ref "XO1") (pin "4") (pinfunction "VCC_4") (pintype "power_in"))
    )
    (net (code "3") (name "BOOT_LED") (class "Default")
      (node (ref "IC10") (pin "3") (pinfunction "PA02_3") (pintype "bidirectional"))
      (node (ref "R60") (pin "1") (pinfunction "1_1") (pintype "passive"))
    )
    (net (code "4") (name "CBSEL0") (class "Default")
      (node (ref "IC10") (pin "8") (pinfunction "PB09_8") (pintype "bidirectional"))
      (node (ref "IC6") (pin "63") (pinfunction "IOB_42_CBSEL0_63") (pintype "bidirectional"))
      (node (ref "R57") (pin "2") (pinfunction "2_2") (pintype "passive"))
    )
    (net (code "5") (name "CBSEL1") (class "Default")
      (node (ref "IC10") (pin "7") (pinfunction "PB08_7") (pintype "bidirectional"))
      (node (ref "IC6") (pin "64") (pinfunction "IOB_43_CBSEL1_64") (pintype "bidirectional"))
      (node (ref "R58") (pin "2") (pinfunction "2_2") (pintype "passive"))
    )
    (net (code "6") (name "CFGDIP0") (class "Default")
      (node (ref "IC6") (pin "9") (pinfunction "IOL_4A_9") (pintype "bidirectional"))
      (node (ref "RN2") (pin "8") (pinfunction "B1_8") (pintype "passive"))
      (node (ref "S1") (pin "8") (pinfunction "2_8") (pintype "passive"))
    )
    (net (code "7") (name "CFGDIP1") (class "Default")
      (node (ref "IC6") (pin "10") (pinfunction "IOL_4B_10") (pintype "bidirectional"))
      (node (ref "RN2") (pin "7") (pinfunction "B2_7") (pintype "passive"))
      (node (ref "S1") (pin "7") (pinfunction "2_7") (pintype "passive"))
    )
    (net (code "8") (name "CFGDIP2") (class "Default")
      (node (ref "IC6") (pin "11") (pinfunction "IOL_5A_11") (pintype "bidirectional"))
      (node (ref "RN2") (pin "6") (pinfunction "B3_6") (pintype "passive"))
      (node (ref "S1") (pin "6") (pinfunction "2_6") (pintype "passive"))
    )
    (net (code "9") (name "CFGDIP3") (class "Default")
      (node (ref "IC6") (pin "12") (pinfunction "IOL_5B_12") (pintype "bidirectional"))
      (node (ref "RN2") (pin "5") (pinfunction "B4_5") (pintype "passive"))
      (node (ref "S1") (pin "5") (pinfunction "2_5") (pintype "passive"))
    )
    (net (code "10") (name "CFG_CK") (class "Default")
      (node (ref "IC8") (pin "6") (pinfunction "CLK_6") (pintype "bidirectional"))
      (node (ref "RN5") (pin "6") (pinfunction "B3_6") (pintype "passive"))
      (node (ref "RN6") (pin "2") (pinfunction "A2_2") (pintype "passive"))
    )
    (net (code "11") (name "CFG_DI") (class "Default")
      (node (ref "IC8") (pin "2") (pinfunction "DO/IO1_2") (pintype "bidirectional"))
      (node (ref "RN5") (pin "7") (pinfunction "B2_7") (pintype "passive"))
      (node (ref "RN6") (pin "3") (pinfunction "A3_3") (pintype "passive"))
    )
    (net (code "12") (name "CFG_DO") (class "Default")
      (node (ref "IC8") (pin "5") (pinfunction "DI/IO0_5") (pintype "bidirectional"))
      (node (ref "RN5") (pin "8") (pinfunction "B1_8") (pintype "passive"))
      (node (ref "RN6") (pin "1") (pinfunction "A1_1") (pintype "passive"))
    )
    (net (code "13") (name "CK27M_INT") (class "Default")
      (node (ref "IC6") (pin "129") (pinfunction "IOT_85_GBIN0_129") (pintype "bidirectional"))
      (node (ref "R12") (pin "1") (pinfunction "1_1") (pintype "passive"))
    )
    (net (code "14") (name "CLED0") (class "Default")
      (node (ref "IC6") (pin "144") (pinfunction "IOT_96_144") (pintype "bidirectional"))
      (node (ref "LED5") (pin "C") (pinfunction "C_C") (pintype "passive"))
    )
    (net (code "15") (name "CLED1") (class "Default")
      (node (ref "IC6") (pin "139") (pinfunction "IOT_92_139") (pintype "bidirectional"))
      (node (ref "LED4") (pin "C") (pinfunction "C_C") (pintype "passive"))
    )
    (net (code "16") (name "CLED2") (class "Default")
      (node (ref "IC6") (pin "141") (pinfunction "IOT_93_141") (pintype "bidirectional"))
      (node (ref "LED3") (pin "C") (pinfunction "C_C") (pintype "passive"))
    )
    (net (code "17") (name "CLED3") (class "Default")
      (node (ref "IC6") (pin "142") (pinfunction "IOT_94_142") (pintype "bidirectional"))
      (node (ref "LED2") (pin "C") (pinfunction "C_C") (pintype "passive"))
    )
    (net (code "18") (name "CLED4") (class "Default")
      (node (ref "IC6") (pin "143") (pinfunction "IOT_95_143") (pintype "bidirectional"))
      (node (ref "LED1") (pin "C") (pinfunction "C_C") (pintype "passive"))
    )
    (net (code "19") (name "EXT_SCL") (class "Default")
      (node (ref "IC10") (pin "26") (pinfunction "PA17_26") (pintype "bidirectional"))
      (node (ref "JP1") (pin "28") (pinfunction "28_28") (pintype "passive"))
      (node (ref "R49") (pin "1") (pinfunction "1_1") (pintype "passive"))
      (node (ref "R51") (pin "1") (pinfunction "1_1") (pintype "passive"))
    )
    (net (code "20") (name "EXT_SDA") (class "Default")
      (node (ref "IC10") (pin "25") (pinfunction "PA16_25") (pintype "bidirectional"))
      (node (ref "JP1") (pin "26") (pinfunction "26_26") (pintype "passive"))
      (node (ref "R48") (pin "1") (pinfunction "1_1") (pintype "passive"))
      (node (ref "R50") (pin "1") (pinfunction "1_1") (pintype "passive"))
    )
    (net (code "21") (name "FLASH_MISO") (class "Default")
      (node (ref "IC10") (pin "15") (pinfunction "PA10_15") (pintype "bidirectional"))
      (node (ref "JP2") (pin "8") (pinfunction "8_8") (pintype "passive"))
      (node (ref "RN6") (pin "6") (pinfunction "B3_6") (pintype "passive"))
    )
    (net (code "22") (name "FLASH_MOSI") (class "Default")
      (node (ref "IC10") (pin "16") (pinfunction "PA11_16") (pintype "bidirectional"))
      (node (ref "JP2") (pin "7") (pinfunction "7_7") (pintype "passive"))
      (node (ref "RN6") (pin "8") (pinfunction "B1_8") (pintype "passive"))
    )
    (net (code "23") (name "FLASH_SCK") (class "Default")
      (node (ref "IC10") (pin "14") (pinfunction "PA09_14") (pintype "bidirectional"))
      (node (ref "JP2") (pin "9") (pinfunction "9_9") (pintype "passive"))
      (node (ref "RN6") (pin "7") (pinfunction "B2_7") (pintype "passive"))
    )
    (net (code "24") (name "FPGA_CDONE") (class "Default")
      (node (ref "IC10") (pin "30") (pinfunction "PA21_30") (pintype "bidirectional"))
      (node (ref "IC6") (pin "65") (pinfunction "CDONE_65") (pintype "bidirectional"))
      (node (ref "JP2") (pin "5") (pinfunction "5_5") (pintype "passive"))
      (node (ref "R43") (pin "1") (pinfunction "1_1") (pintype "passive"))
    )
    (net (code "25") (name "FPGA_SCL") (class "Default")
      (node (ref "IC6") (pin "20") (pinfunction "IOL_6B_GBIN7_20") (pintype "bidirectional"))
      (node (ref "R54") (pin "1") (pinfunction "1_1") (pintype "passive"))
    )
    (net (code "26") (name "FPGA_SDA") (class "Default")
      (node (ref "IC6") (pin "19") (pinfunction "IOL_6A_19") (pintype "bidirectional"))
      (node (ref "R55") (pin "1") (pinfunction "1_1") (pintype "passive"))
    )
    (net (code "27") (name "GND") (class "Default")
      (node (ref "C10") (pin "2") (pinfunction "2_2") (pintype "passive"))
      (node (ref "C11") (pin "2") (pinfunction "2_2") (pintype "passive"))
      (node (ref "C12") (pin "2") (pinfunction "2_2") (pintype "passive"))
      (node (ref "C13") (pin "2") (pinfunction "2_2") (pintype "passive"))
      (node (ref "C14") (pin "2") (pinfunction "2_2") (pintype "passive"))
      (node (ref "C15") (pin "2") (pinfunction "2_2") (pintype "passive"))
      (node (ref "C16") (pin "2") (pinfunction "2_2") (pintype "passive"))
      (node (ref "C17") (pin "2") (pinfunction "2_2") (pintype "passive"))
      (node (ref "C18") (pin "1") (pinfunction "1_1") (pintype "passive"))
      (node (ref "C20") (pin "2") (pinfunction "2_2") (pintype "passive"))
      (node (ref "C21") (pin "2") (pinfunction "2_2") (pintype "passive"))
      (node (ref "C22") (pin "2") (pinfunction "2_2") (pintype "passive"))
      (node (ref "C23") (pin "-") (pinfunction "-_-") (pintype "passive"))
      (node (ref "C24") (pin "-") (pinfunction "-_-") (pintype "passive"))
      (node (ref "C25") (pin "2") (pinfunction "2_2") (pintype "passive"))
      (node (ref "C27") (pin "2") (pinfunction "2_2") (pintype "passive"))
      (node (ref "C28") (pin "2") (pinfunction "2_2") (pintype "passive"))
      (node (ref "C29") (pin "2") (pinfunction "2_2") (pintype "passive"))
      (node (ref "C30") (pin "2") (pinfunction "2_2") (pintype "passive"))
      (node (ref "C31") (pin "2") (pinfunction "2_2") (pintype "passive"))
      (node (ref "C317") (pin "2") (pinfunction "2_2") (pintype "passive"))
      (node (ref "C318") (pin "2") (pinfunction "2_2") (pintype "passive"))
      (node (ref "C319") (pin "2") (pinfunction "2_2") (pintype "passive"))
      (node (ref "C32") (pin "2") (pinfunction "2_2") (pintype "passive"))
      (node (ref "C33") (pin "2") (pinfunction "2_2") (pintype "passive"))
      (node (ref "C34") (pin "2") (pinfunction "2_2") (pintype "passive"))
      (node (ref "C35") (pin "2") (pinfunction "2_2") (pintype "passive"))
      (node (ref "C36") (pin "2") (pinfunction "2_2") (pintype "passive"))
      (node (ref "C37") (pin "2") (pinfunction "2_2") (pintype "passive"))
      (node (ref "C38") (pin "2") (pinfunction "2_2") (pintype "passive"))
      (node (ref "C39") (pin "2") (pinfunction "2_2") (pintype "passive"))
      (node (ref "C40") (pin "2") (pinfunction "2_2") (pintype "passive"))
      (node (ref "C41") (pin "2") (pinfunction "2_2") (pintype "passive"))
      (node (ref "C42") (pin "2") (pinfunction "2_2") (pintype "passive"))
      (node (ref "C44") (pin "2") (pinfunction "2_2") (pintype "passive"))
      (node (ref "C45") (pin "2") (pinfunction "2_2") (pintype "passive"))
      (node (ref "C48") (pin "-") (pinfunction "-_-") (pintype "passive"))
      (node (ref "C49") (pin "2") (pinfunction "2_2") (pintype "passive"))
      (node (ref "C50") (pin "2") (pinfunction "2_2") (pintype "passive"))
      (node (ref "C51") (pin "-") (pinfunction "-_-") (pintype "passive"))
      (node (ref "C54") (pin "2") (pinfunction "2_2") (pintype "passive"))
      (node (ref "C55") (pin "2") (pinfunction "2_2") (pintype "passive"))
      (node (ref "C56") (pin "2") (pinfunction "2_2") (pintype "passive"))
      (node (ref "C57") (pin "-") (pinfunction "-_-") (pintype "passive"))
      (node (ref "C58") (pin "2") (pinfunction "2_2") (pintype "passive"))
      (node (ref "C59") (pin "2") (pinfunction "2_2") (pintype "passive"))
      (node (ref "C60") (pin "2") (pinfunction "2_2") (pintype "passive"))
      (node (ref "C61") (pin "2") (pinfunction "2_2") (pintype "passive"))
      (node (ref "C62") (pin "2") (pinfunction "2_2") (pintype "passive"))
      (node (ref "C63") (pin "2") (pinfunction "2_2") (pintype "passive"))
      (node (ref "C64") (pin "2") (pinfunction "2_2") (pintype "passive"))
      (node (ref "C65") (pin "-") (pinfunction "-_-") (pintype "passive"))
      (node (ref "C66") (pin "-") (pinfunction "-_-") (pintype "passive"))
      (node (ref "C67") (pin "2") (pinfunction "2_2") (pintype "passive"))
      (node (ref "C68") (pin "2") (pinfunction "2_2") (pintype "passive"))
      (node (ref "C69") (pin "2") (pinfunction "2_2") (pintype "passive"))
      (node (ref "C70") (pin "2") (pinfunction "2_2") (pintype "passive"))
      (node (ref "C71") (pin "2") (pinfunction "2_2") (pintype "passive"))
      (node (ref "C8") (pin "2") (pinfunction "2_2") (pintype "passive"))
      (node (ref "C9") (pin "2") (pinfunction "2_2") (pintype "passive"))
      (node (ref "CN1") (pin "2") (pinfunction "GND_2") (pintype "power_in"))
      (node (ref "CN2") (pin "2") (pinfunction "GND_2") (pintype "power_in"))
      (node (ref "CN3") (pin "2") (pinfunction "GND_2") (pintype "power_in"))
      (node (ref "CN4") (pin "2") (pinfunction "2_2") (pintype "bidirectional"))
      (node (ref "CN5") (pin "5") (pinfunction "GND_5") (pintype "bidirectional"))
      (node (ref "CN5") (pin "GND1") (pinfunction "SHLD_GND1") (pintype "passive"))
      (node (ref "CN5") (pin "GND2") (pinfunction "SHLD_GND2") (pintype "passive"))
      (node (ref "CN5") (pin "GND3") (pinfunction "SHLD_GND3") (pintype "passive"))
      (node (ref "CN5") (pin "GND4") (pinfunction "SHLD_GND4") (pintype "passive"))
      (node (ref "CN6") (pin "1") (pinfunction "1_1") (pintype "bidirectional"))
      (node (ref "CN7") (pin "2") (pinfunction "2_2") (pintype "bidirectional"))
      (node (ref "CN8") (pin "1") (pinfunction "1_1") (pintype "bidirectional"))
      (node (ref "IC1") (pin "10") (pinfunction "GND_10") (pintype "power_in"))
      (node (ref "IC1") (pin "2") (pinfunction "GND_2") (pintype "power_in"))
      (node (ref "IC1") (pin "5") (pinfunction "GND_5") (pintype "power_in"))
      (node (ref "IC10") (pin "18") (pinfunction "GND_18") (pintype "passive"))
      (node (ref "IC10") (pin "35") (pinfunction "GND_35") (pintype "passive"))
      (node (ref "IC10") (pin "42") (pinfunction "GND_42") (pintype "passive"))
      (node (ref "IC10") (pin "5") (pinfunction "AGND_5") (pintype "passive"))
      (node (ref "IC2") (pin "16") (pinfunction "EQDIS_16") (pintype "input"))
      (node (ref "IC2") (pin "3") (pinfunction "GND_3") (pintype "power_in"))
      (node (ref "IC2") (pin "TP") (pinfunction "GND_TP") (pintype "power_in"))
      (node (ref "IC3") (pin "19") (pinfunction "DGND_19") (pintype "power_in"))
      (node (ref "IC3") (pin "3") (pinfunction "PLL_AGND_3") (pintype "power_in"))
      (node (ref "IC3") (pin "31") (pinfunction "CH_AGND_31") (pintype "power_in"))
      (node (ref "IC3") (pin "7") (pinfunction "AGND_7") (pintype "power_in"))
      (node (ref "IC305") (pin "2") (pinfunction "GND_2") (pintype "power_in"))
      (node (ref "IC4") (pin "1") (pinfunction "OE_1") (pintype "input"))
      (node (ref "IC4") (pin "3") (pinfunction "GND_3") (pintype "power_in"))
      (node (ref "IC5") (pin "12") (pinfunction "GND_12") (pintype "power_in"))
      (node (ref "IC5") (pin "34") (pinfunction "GND_34") (pintype "power_in"))
      (node (ref "IC6") (pin "103") (pinfunction "GND_103") (pintype "power_in"))
      (node (ref "IC6") (pin "13") (pinfunction "GND_13") (pintype "power_in"))
      (node (ref "IC6") (pin "132") (pinfunction "GND_132") (pintype "power_in"))
      (node (ref "IC6") (pin "14") (pinfunction "GND_14") (pintype "power_in"))
      (node (ref "IC6") (pin "140") (pinfunction "GND_140") (pintype "power_in"))
      (node (ref "IC6") (pin "5") (pinfunction "GND_5") (pintype "power_in"))
      (node (ref "IC6") (pin "59") (pinfunction "GND_59") (pintype "power_in"))
      (node (ref "IC6") (pin "69") (pinfunction "GND_69") (pintype "power_in"))
      (node (ref "IC6") (pin "86") (pinfunction "GND_86") (pintype "power_in"))
      (node (ref "IC7") (pin "2") (pinfunction "GND_2") (pintype "power_in"))
      (node (ref "IC8") (pin "4") (pinfunction "GND_4") (pintype "bidirectional"))
      (node (ref "IC9") (pin "1") (pinfunction "GND_1") (pintype "power_in"))
      (node (ref "JP1") (pin "11") (pinfunction "11_11") (pintype "passive"))
      (node (ref "JP1") (pin "13") (pinfunction "13_13") (pintype "passive"))
      (node (ref "JP1") (pin "15") (pinfunction "15_15") (pintype "passive"))
      (node (ref "JP1") (pin "17") (pinfunction "17_17") (pintype "passive"))
      (node (ref "JP1") (pin "19") (pinfunction "19_19") (pintype "passive"))
      (node (ref "JP1") (pin "21") (pinfunction "21_21") (pintype "passive"))
      (node (ref "JP1") (pin "23") (pinfunction "23_23") (pintype "passive"))
      (node (ref "JP1") (pin "25") (pinfunction "25_25") (pintype "passive"))
      (node (ref "JP1") (pin "27") (pinfunction "27_27") (pintype "passive"))
      (node (ref "JP1") (pin "3") (pinfunction "3_3") (pintype "passive"))
      (node (ref "JP1") (pin "5") (pinfunction "5_5") (pintype "passive"))
      (node (ref "JP1") (pin "7") (pinfunction "7_7") (pintype "passive"))
      (node (ref "JP1") (pin "9") (pinfunction "9_9") (pintype "passive"))
      (node (ref "JP2") (pin "1") (pinfunction "1_1") (pintype "passive"))
      (node (ref "JP3") (pin "3") (pinfunction "3_3") (pintype "passive"))
      (node (ref "JP3") (pin "5") (pinfunction "5_5") (pintype "passive"))
      (node (ref "JP3") (pin "9") (pinfunction "9_9") (pintype "passive"))
      (node (ref "Q1") (pin "2") (pinfunction "G1_2") (pintype "passive"))
      (node (ref "Q1") (pin "4") (pinfunction "G2_4") (pintype "passive"))
      (node (ref "Q3") (pin "2") (pinfunction "G1_2") (pintype "passive"))
      (node (ref "Q3") (pin "4") (pinfunction "G2_4") (pintype "passive"))
      (node (ref "R11") (pin "2") (pinfunction "2_2") (pintype "passive"))
      (node (ref "R28") (pin "1") (pinfunction "1_1") (pintype "passive"))
      (node (ref "R31") (pin "1") (pinfunction "1_1") (pintype "passive"))
      (node (ref "R32") (pin "1") (pinfunction "1_1") (pintype "passive"))
      (node (ref "R39") (pin "1") (pinfunction "1_1") (pintype "passive"))
      (node (ref "R40") (pin "1") (pinfunction "1_1") (pintype "passive"))
      (node (ref "R42") (pin "1") (pinfunction "1_1") (pintype "passive"))
      (node (ref "R5") (pin "1") (pinfunction "1_1") (pintype "passive"))
      (node (ref "R56") (pin "1") (pinfunction "1_1") (pintype "passive"))
      (node (ref "R57") (pin "1") (pinfunction "1_1") (pintype "passive"))
      (node (ref "R58") (pin "1") (pinfunction "1_1") (pintype "passive"))
      (node (ref "R8") (pin "2") (pinfunction "2_2") (pintype "passive"))
      (node (ref "R9") (pin "2") (pinfunction "2_2") (pintype "passive"))
      (node (ref "S1") (pin "1") (pinfunction "1_1") (pintype "passive"))
      (node (ref "S1") (pin "2") (pinfunction "1_2") (pintype "passive"))
      (node (ref "S1") (pin "3") (pinfunction "1_3") (pintype "passive"))
      (node (ref "S1") (pin "4") (pinfunction "1_4") (pintype "passive"))
      (node (ref "SW1") (pin "1") (pinfunction "P_1") (pintype "passive"))
      (node (ref "SW1") (pin "2") (pinfunction "P1_2") (pintype "passive"))
      (node (ref "T1") (pin "2") (pinfunction "S_2") (pintype "passive"))
      (node (ref "X1") (pin "2") (pinfunction "GND_2") (pintype "power_in"))
      (node (ref "X2") (pin "2") (pinfunction "GND_2") (pintype "power_in"))
      (node (ref "XO1") (pin "2") (pinfunction "GND_2") (pintype "power_in"))
    )
    (net (code "28") (name "LMH_HS") (class "Default")
      (node (ref "IC6") (pin "1") (pinfunction "IOL_1A_1") (pintype "bidirectional"))
      (node (ref "RN7") (pin "8") (pinfunction "B1_8") (pintype "passive"))
    )
    (net (code "29") (name "LMH_OE") (class "Default")
      (node (ref "IC6") (pin "4") (pinfunction "IOL_2B_4") (pintype "bidirectional"))
      (node (ref "RN7") (pin "5") (pinfunction "B4_5") (pintype "passive"))
    )
    (net (code "30") (name "LMH_VF") (class "Default")
      (node (ref "IC6") (pin "3") (pinfunction "IOL_2A_3") (pintype "bidirectional"))
      (node (ref "RN7") (pin "6") (pinfunction "B3_6") (pintype "passive"))
    )
    (net (code "31") (name "LMH_VS") (class "Default")
      (node (ref "IC6") (pin "2") (pinfunction "IOL_1B_2") (pintype "bidirectional"))
      (node (ref "RN7") (pin "7") (pinfunction "B2_7") (pintype "passive"))
    )
    (net (code "32") (name "Net-(C1-Pad1)") (class "Default")
      (node (ref "C1") (pin "1") (pinfunction "1_1") (pintype "passive"))
      (node (ref "R1") (pin "2") (pinfunction "2_2") (pintype "passive"))
      (node (ref "R2") (pin "2") (pinfunction "2_2") (pintype "passive"))
    )
    (net (code "33") (name "Net-(C2-Pad1)") (class "Default")
      (node (ref "C2") (pin "1") (pinfunction "1_1") (pintype "passive"))
      (node (ref "R1") (pin "1") (pinfunction "1_1") (pintype "passive"))
      (node (ref "R3") (pin "2") (pinfunction "2_2") (pintype "passive"))
    )
    (net (code "34") (name "Net-(C3-Pad2)") (class "Default")
      (node (ref "C3") (pin "2") (pinfunction "2_2") (pintype "passive"))
      (node (ref "R4") (pin "1") (pinfunction "1_1") (pintype "passive"))
      (node (ref "R9") (pin "1") (pinfunction "1_1") (pintype "passive"))
    )
    (net (code "35") (name "Net-(C4-Pad1)") (class "Default")
      (node (ref "C4") (pin "1") (pinfunction "1_1") (pintype "passive"))
      (node (ref "R6") (pin "2") (pinfunction "2_2") (pintype "passive"))
    )
    (net (code "36") (name "Net-(C4-Pad2)") (class "Default")
      (node (ref "C4") (pin "2") (pinfunction "2_2") (pintype "passive"))
      (node (ref "CN2") (pin "1") (pinfunction "1_1") (pintype "passive"))
    )
    (net (code "37") (name "Net-(C5-Pad1)") (class "Default")
      (node (ref "C5") (pin "1") (pinfunction "1_1") (pintype "passive"))
      (node (ref "R7") (pin "2") (pinfunction "2_2") (pintype "passive"))
    )
    (net (code "38") (name "Net-(C5-Pad2)") (class "Default")
      (node (ref "C5") (pin "2") (pinfunction "2_2") (pintype "passive"))
      (node (ref "CN3") (pin "1") (pinfunction "1_1") (pintype "passive"))
    )
    (net (code "39") (name "Net-(C6-Pad2)") (class "Default")
      (node (ref "C6") (pin "2") (pinfunction "2_2") (pintype "passive"))
      (node (ref "R8") (pin "1") (pinfunction "1_1") (pintype "passive"))
    )
    (net (code "40") (name "Net-(C7-Pad2)") (class "Default")
      (node (ref "C7") (pin "2") (pinfunction "2_2") (pintype "passive"))
      (node (ref "R24") (pin "1") (pinfunction "1_1") (pintype "passive"))
    )
    (net (code "41") (name "Net-(C19-Pad1)") (class "Default")
      (node (ref "C19") (pin "1") (pinfunction "1_1") (pintype "passive"))
      (node (ref "R28") (pin "2") (pinfunction "2_2") (pintype "passive"))
      (node (ref "R29") (pin "2") (pinfunction "2_2") (pintype "passive"))
    )
    (net (code "42") (name "Net-(C20-Pad1)") (class "Default")
      (node (ref "C20") (pin "1") (pinfunction "1_1") (pintype "passive"))
      (node (ref "C52") (pin "1") (pinfunction "1_1") (pintype "passive"))
      (node (ref "R29") (pin "1") (pinfunction "1_1") (pintype "passive"))
      (node (ref "R30") (pin "2") (pinfunction "2_2") (pintype "passive"))
      (node (ref "R40") (pin "2") (pinfunction "2_2") (pintype "passive"))
    )
    (net (code "43") (name "Net-(C53-Pad1)") (class "Default")
      (node (ref "C53") (pin "1") (pinfunction "1_1") (pintype "passive"))
      (node (ref "CN4") (pin "1") (pinfunction "1_1") (pintype "bidirectional"))
    )
    (net (code "44") (name "Net-(CN1-Pad1)") (class "Default")
      (node (ref "CN1") (pin "1") (pinfunction "1_1") (pintype "passive"))
      (node (ref "R30") (pin "1") (pinfunction "1_1") (pintype "passive"))
    )
    (net (code "45") (name "Net-(CN5-VBUS)") (class "Default")
      (node (ref "CN5") (pin "1") (pinfunction "VBUS_1") (pintype "bidirectional"))
      (node (ref "D2") (pin "A") (pinfunction "A_A") (pintype "passive"))
    )
    (net (code "46") (name "Net-(CN6-Pad4)") (class "Default")
      (node (ref "CN6") (pin "4") (pinfunction "4_4") (pintype "bidirectional"))
      (node (ref "R45") (pin "1") (pinfunction "1_1") (pintype "passive"))
    )
    (net (code "47") (name "Net-(D1-C)") (class "Default")
      (node (ref "C55") (pin "1") (pinfunction "1_1") (pintype "passive"))
      (node (ref "D1") (pin "K") (pinfunction "C_K") (pintype "passive"))
      (node (ref "IC6") (pin "108") (pinfunction "VPP_2V5_108") (pintype "power_in"))
    )
    (net (code "48") (name "Net-(IC1-HSOUT)") (class "Default")
      (node (ref "IC1") (pin "7") (pinfunction "HSOUT_7") (pintype "output"))
      (node (ref "RN7") (pin "1") (pinfunction "A1_1") (pintype "passive"))
    )
    (net (code "49") (name "Net-(IC1-OEOUT)") (class "Default")
      (node (ref "IC1") (pin "14") (pinfunction "OEOUT_14") (pintype "output"))
      (node (ref "RN7") (pin "4") (pinfunction "A4_4") (pintype "passive"))
    )
    (net (code "50") (name "Net-(IC1-REXT)") (class "Default")
      (node (ref "IC1") (pin "1") (pinfunction "REXT_1") (pintype "passive"))
      (node (ref "R39") (pin "2") (pinfunction "2_2") (pintype "passive"))
    )
    (net (code "51") (name "Net-(IC1-VFOUT)") (class "Default")
      (node (ref "IC1") (pin "9") (pinfunction "VFOUT_9") (pintype "output"))
      (node (ref "RN7") (pin "3") (pinfunction "A3_3") (pintype "passive"))
    )
    (net (code "52") (name "Net-(IC1-VIN)") (class "Default")
      (node (ref "C52") (pin "2") (pinfunction "2_2") (pintype "passive"))
      (node (ref "C53") (pin "2") (pinfunction "2_2") (pintype "passive"))
      (node (ref "IC1") (pin "4") (pinfunction "VIN_4") (pintype "input"))
    )
    (net (code "53") (name "Net-(IC1-VSOUT)") (class "Default")
      (node (ref "IC1") (pin "8") (pinfunction "VSOUT_8") (pintype "output"))
      (node (ref "RN7") (pin "2") (pinfunction "A2_2") (pintype "passive"))
    )
    (net (code "54") (name "Net-(IC2-ENABLE)") (class "Default")
      (node (ref "C22") (pin "1") (pinfunction "1_1") (pintype "passive"))
      (node (ref "C48") (pin "+") (pinfunction "+_+") (pintype "passive"))
      (node (ref "FB2") (pin "2") (pinfunction "2_2") (pintype "passive"))
      (node (ref "IC2") (pin "10") (pinfunction "SD/~{HD}_10") (pintype "passive"))
      (node (ref "IC2") (pin "6") (pinfunction "ENABLE_6") (pintype "input"))
      (node (ref "IC2") (pin "9") (pinfunction "VCC_9") (pintype "power_in"))
      (node (ref "R38") (pin "1") (pinfunction "1_1") (pintype "passive"))
    )
    (net (code "55") (name "Net-(IC2-RREF)") (class "Default")
      (node (ref "IC2") (pin "4") (pinfunction "RREF_4") (pintype "passive"))
      (node (ref "R38") (pin "2") (pinfunction "2_2") (pintype "passive"))
    )
    (net (code "56") (name "Net-(IC2-SDI)") (class "Default")
      (node (ref "C1") (pin "2") (pinfunction "2_2") (pintype "passive"))
      (node (ref "IC2") (pin "1") (pinfunction "SDI_1") (pintype "bidirectional"))
    )
    (net (code "57") (name "Net-(IC2-SDO)") (class "Default")
      (node (ref "IC2") (pin "12") (pinfunction "SDO_12") (pintype "bidirectional"))
      (node (ref "R6") (pin "1") (pinfunction "1_1") (pintype "passive"))
    )
    (net (code "58") (name "Net-(IC2-~{SDI})") (class "Default")
      (node (ref "C2") (pin "2") (pinfunction "2_2") (pintype "passive"))
      (node (ref "IC2") (pin "2") (pinfunction "~{SDI}_2") (pintype "bidirectional"))
    )
    (net (code "59") (name "Net-(IC2-~{SDO})") (class "Default")
      (node (ref "IC2") (pin "11") (pinfunction "~{SDO}_11") (pintype "bidirectional"))
      (node (ref "R7") (pin "1") (pinfunction "1_1") (pintype "passive"))
    )
    (net (code "60") (name "Net-(IC3A-AIP1A)") (class "Default")
      (node (ref "C18") (pin "2") (pinfunction "2_2") (pintype "passive"))
      (node (ref "IC3") (pin "1") (pinfunction "AIP1A_1") (pintype "input"))
    )
    (net (code "61") (name "Net-(IC3A-AIP1B)") (class "Default")
      (node (ref "C19") (pin "2") (pinfunction "2_2") (pintype "passive"))
      (node (ref "IC3") (pin "2") (pinfunction "AIP1B_2") (pintype "input"))
    )
    (net (code "62") (name "Net-(IC3A-AVID{slash}CKIN)") (class "Default")
      (node (ref "IC3") (pin "26") (pinfunction "AVID/CKIN_26") (pintype "output"))
      (node (ref "R32") (pin "2") (pinfunction "2_2") (pintype "passive"))
    )
    (net (code "63") (name "Net-(IC3A-IRQ{slash}GPCL{slash}VBLK{slash}PALI)") (class "Default")
      (node (ref "IC3") (pin "27") (pinfunction "IRQ/GPCL/VBLK/PALI_27") (pintype "output"))
      (node (ref "R31") (pin "2") (pinfunction "2_2") (pintype "passive"))
    )
    (net (code "64") (name "Net-(IC3A-SCLK)") (class "Default")
      (node (ref "IC3") (pin "9") (pinfunction "SCLK_9") (pintype "output"))
      (node (ref "R26") (pin "1") (pinfunction "1_1") (pintype "passive"))
    )
    (net (code "65") (name "Net-(IC3A-XTAL1{slash}OSC)") (class "Default")
      (node (ref "C15") (pin "1") (pinfunction "1_1") (pintype "passive"))
      (node (ref "IC3") (pin "5") (pinfunction "XTAL1/OSC_5") (pintype "passive"))
      (node (ref "Q1") (pin "3") (pinfunction "2_3") (pintype "passive"))
      (node (ref "R34") (pin "1") (pinfunction "1_1") (pintype "passive"))
    )
    (net (code "66") (name "Net-(IC3A-XTAL2)") (class "Default")
      (node (ref "C14") (pin "1") (pinfunction "1_1") (pintype "passive"))
      (node (ref "IC3") (pin "6") (pinfunction "XTAL2_6") (pintype "passive"))
      (node (ref "Q1") (pin "1") (pinfunction "1_1") (pintype "passive"))
      (node (ref "R34") (pin "2") (pinfunction "2_2") (pintype "passive"))
    )
    (net (code "67") (name "Net-(IC3A-YOUT0)") (class "Default")
      (node (ref "IC3") (pin "18") (pinfunction "YOUT0_18") (pintype "output"))
      (node (ref "RN3") (pin "1") (pinfunction "A1_1") (pintype "passive"))
    )
    (net (code "68") (name "Net-(IC3A-YOUT1)") (class "Default")
      (node (ref "IC3") (pin "17") (pinfunction "YOUT1_17") (pintype "output"))
      (node (ref "RN3") (pin "2") (pinfunction "A2_2") (pintype "passive"))
    )
    (net (code "69") (name "Net-(IC3A-YOUT2)") (class "Default")
      (node (ref "IC3") (pin "16") (pinfunction "YOUT2_16") (pintype "output"))
      (node (ref "RN3") (pin "3") (pinfunction "A3_3") (pintype "passive"))
    )
    (net (code "70") (name "Net-(IC3A-YOUT3)") (class "Default")
      (node (ref "IC3") (pin "15") (pinfunction "YOUT3_15") (pintype "output"))
      (node (ref "RN3") (pin "4") (pinfunction "A4_4") (pintype "passive"))
    )
    (net (code "71") (name "Net-(IC3A-YOUT4)") (class "Default")
      (node (ref "IC3") (pin "14") (pinfunction "YOUT4_14") (pintype "output"))
      (node (ref "RN4") (pin "1") (pinfunction "A1_1") (pintype "passive"))
    )
    (net (code "72") (name "Net-(IC3A-YOUT5)") (class "Default")
      (node (ref "IC3") (pin "13") (pinfunction "YOUT5_13") (pintype "output"))
      (node (ref "RN4") (pin "2") (pinfunction "A2_2") (pintype "passive"))
    )
    (net (code "73") (name "Net-(IC3A-YOUT6)") (class "Default")
      (node (ref "IC3") (pin "12") (pinfunction "YOUT6_12") (pintype "output"))
      (node (ref "RN4") (pin "3") (pinfunction "A3_3") (pintype "passive"))
    )
    (net (code "74") (name "Net-(IC3A-YOUT7)") (class "Default")
      (node (ref "IC3") (pin "11") (pinfunction "YOUT7_11") (pintype "output"))
      (node (ref "RN4") (pin "4") (pinfunction "A4_4") (pintype "passive"))
    )
    (net (code "75") (name "Net-(IC3B-CH_AVDD)") (class "Default")
      (node (ref "C16") (pin "1") (pinfunction "1_1") (pintype "passive"))
      (node (ref "C21") (pin "1") (pinfunction "1_1") (pintype "passive"))
      (node (ref "C24") (pin "+") (pinfunction "+_+") (pintype "passive"))
      (node (ref "IC3") (pin "32") (pinfunction "CH_AVDD_32") (pintype "power_in"))
      (node (ref "IC3") (pin "4") (pinfunction "PLL_AVCC_4") (pintype "power_in"))
      (node (ref "L2") (pin "1") (pinfunction "1_1") (pintype "passive"))
      (node (ref "R33") (pin "2") (pinfunction "2_2") (pintype "passive"))
    )
    (net (code "76") (name "Net-(IC3B-REFM)") (class "Default")
      (node (ref "C26") (pin "2") (pinfunction "2_2") (pintype "passive"))
      (node (ref "C28") (pin "1") (pinfunction "1_1") (pintype "passive"))
      (node (ref "IC3") (pin "30") (pinfunction "REFM_30") (pintype "passive"))
    )
    (net (code "77") (name "Net-(IC3B-REFP)") (class "Default")
      (node (ref "C26") (pin "1") (pinfunction "1_1") (pintype "passive"))
      (node (ref "C27") (pin "1") (pinfunction "1_1") (pintype "passive"))
      (node (ref "IC3") (pin "29") (pinfunction "REFP_29") (pintype "passive"))
    )
    (net (code "78") (name "Net-(IC4A-I)") (class "Default")
      (node (ref "IC4") (pin "2") (pinfunction "I_2") (pintype "input"))
      (node (ref "R10") (pin "2") (pinfunction "2_2") (pintype "passive"))
    )
    (net (code "79") (name "Net-(IC4A-O)") (class "Default")
      (node (ref "C7") (pin "1") (pinfunction "1_1") (pintype "passive"))
      (node (ref "IC4") (pin "4") (pinfunction "O_4") (pintype "tri_state"))
    )
    (net (code "80") (name "Net-(IC6A-GNDPLL)") (class "Default")
      (node (ref "C46") (pin "2") (pinfunction "2_2") (pintype "passive"))
      (node (ref "C47") (pin "2") (pinfunction "2_2") (pintype "passive"))
      (node (ref "IC6") (pin "35") (pinfunction "GNDPLL_35") (pintype "power_in"))
    )
    (net (code "81") (name "Net-(IC6A-IOB_44_SDO)") (class "Default")
      (node (ref "IC6") (pin "67") (pinfunction "IOB_44_SDO_67") (pintype "bidirectional"))
      (node (ref "RN5") (pin "1") (pinfunction "A1_1") (pintype "passive"))
    )
    (net (code "82") (name "Net-(IC6A-IOB_45_SDI)") (class "Default")
      (node (ref "IC6") (pin "68") (pinfunction "IOB_45_SDI_68") (pintype "bidirectional"))
      (node (ref "RN5") (pin "2") (pinfunction "A2_2") (pintype "passive"))
    )
    (net (code "83") (name "Net-(IC6A-IOB_46_SCK)") (class "Default")
      (node (ref "IC6") (pin "70") (pinfunction "IOB_46_SCK_70") (pintype "bidirectional"))
      (node (ref "RN5") (pin "3") (pinfunction "A3_3") (pintype "passive"))
    )
    (net (code "84") (name "Net-(IC6A-IOB_47_SS)") (class "Default")
      (node (ref "IC6") (pin "71") (pinfunction "IOB_47_SS_71") (pintype "bidirectional"))
      (node (ref "RN5") (pin "4") (pinfunction "A4_4") (pintype "passive"))
    )
    (net (code "85") (name "Net-(IC6A-VCCPLL)") (class "Default")
      (node (ref "C46") (pin "1") (pinfunction "1_1") (pintype "passive"))
      (node (ref "C47") (pin "1") (pinfunction "1_1") (pintype "passive"))
      (node (ref "IC6") (pin "36") (pinfunction "VCCPLL_36") (pintype "power_in"))
      (node (ref "R37") (pin "2") (pinfunction "2_2") (pintype "passive"))
    )
    (net (code "86") (name "Net-(IC8-~{HOLD}{slash}IO3)") (class "Default")
      (node (ref "IC8") (pin "3") (pinfunction "~{WP}/IO2_3") (pintype "bidirectional"))
      (node (ref "IC8") (pin "7") (pinfunction "~{HOLD}/IO3_7") (pintype "bidirectional"))
      (node (ref "R36") (pin "1") (pinfunction "1_1") (pintype "passive"))
    )
    (net (code "87") (name "Net-(IC9-BST)") (class "Default")
      (node (ref "C43") (pin "1") (pinfunction "1_1") (pintype "passive"))
      (node (ref "IC9") (pin "6") (pinfunction "BST_6") (pintype "passive"))
    )
    (net (code "88") (name "Net-(IC9-FB)") (class "Default")
      (node (ref "IC9") (pin "4") (pinfunction "FB_4") (pintype "passive"))
      (node (ref "R41") (pin "1") (pinfunction "1_1") (pintype "passive"))
      (node (ref "R42") (pin "2") (pinfunction "2_2") (pintype "passive"))
    )
    (net (code "89") (name "Net-(IC9-SW)") (class "Default")
      (node (ref "C43") (pin "2") (pinfunction "2_2") (pintype "passive"))
      (node (ref "IC9") (pin "2") (pinfunction "SW_2") (pintype "output"))
      (node (ref "L1") (pin "1") (pinfunction "P$1_1") (pintype "passive"))
    )
    (net (code "90") (name "Net-(IC10A-PA00)") (class "Default")
      (node (ref "C68") (pin "1") (pinfunction "1_1") (pintype "passive"))
      (node (ref "IC10") (pin "1") (pinfunction "PA00_1") (pintype "bidirectional"))
      (node (ref "Q2") (pin "1") (pinfunction "1_1") (pintype "passive"))
    )
    (net (code "91") (name "Net-(IC10A-PA01)") (class "Default")
      (node (ref "C67") (pin "1") (pinfunction "1_1") (pintype "passive"))
      (node (ref "IC10") (pin "2") (pinfunction "PA01_2") (pintype "bidirectional"))
      (node (ref "Q2") (pin "2") (pinfunction "2_2") (pintype "passive"))
    )
    (net (code "92") (name "Net-(IC10A-PA03)") (class "Default")
      (node (ref "IC10") (pin "4") (pinfunction "PA03_4") (pintype "bidirectional"))
      (node (ref "LED7") (pin "C") (pinfunction "C_C") (pintype "passive"))
    )
    (net (code "93") (name "Net-(IC10A-PA14)") (class "Default")
      (node (ref "C70") (pin "1") (pinfunction "1_1") (pintype "passive"))
      (node (ref "IC10") (pin "23") (pinfunction "PA14_23") (pintype "bidirectional"))
      (node (ref "Q3") (pin "3") (pinfunction "2_3") (pintype "passive"))
    )
    (net (code "94") (name "Net-(IC10A-PA15)") (class "Default")
      (node (ref "C69") (pin "1") (pinfunction "1_1") (pintype "passive"))
      (node (ref "IC10") (pin "24") (pinfunction "PA15_24") (pintype "bidirectional"))
      (node (ref "Q3") (pin "1") (pinfunction "1_1") (pintype "passive"))
    )
    (net (code "95") (name "Net-(IC10B-VDDCORE)") (class "Default")
      (node (ref "C61") (pin "1") (pinfunction "1_1") (pintype "passive"))
      (node (ref "IC10") (pin "43") (pinfunction "VDDCORE_43") (pintype "power_in"))
    )
    (net (code "96") (name "Net-(JP1-Pad4)") (class "Default")
      (node (ref "JP1") (pin "4") (pinfunction "4_4") (pintype "passive"))
      (node (ref "R13") (pin "1") (pinfunction "1_1") (pintype "passive"))
    )
    (net (code "97") (name "Net-(JP1-Pad6)") (class "Default")
      (node (ref "JP1") (pin "6") (pinfunction "6_6") (pintype "passive"))
      (node (ref "R14") (pin "1") (pinfunction "1_1") (pintype "passive"))
    )
    (net (code "98") (name "Net-(JP1-Pad8)") (class "Default")
      (node (ref "JP1") (pin "8") (pinfunction "8_8") (pintype "passive"))
      (node (ref "R15") (pin "1") (pinfunction "1_1") (pintype "passive"))
    )
    (net (code "99") (name "Net-(JP1-Pad10)") (class "Default")
      (node (ref "JP1") (pin "10") (pinfunction "10_10") (pintype "passive"))
      (node (ref "R16") (pin "1") (pinfunction "1_1") (pintype "passive"))
    )
    (net (code "100") (name "Net-(JP1-Pad12)") (class "Default")
      (node (ref "JP1") (pin "12") (pinfunction "12_12") (pintype "passive"))
      (node (ref "R17") (pin "1") (pinfunction "1_1") (pintype "passive"))
    )
    (net (code "101") (name "Net-(JP1-Pad14)") (class "Default")
      (node (ref "JP1") (pin "14") (pinfunction "14_14") (pintype "passive"))
      (node (ref "R18") (pin "1") (pinfunction "1_1") (pintype "passive"))
    )
    (net (code "102") (name "Net-(JP1-Pad16)") (class "Default")
      (node (ref "JP1") (pin "16") (pinfunction "16_16") (pintype "passive"))
      (node (ref "R19") (pin "1") (pinfunction "1_1") (pintype "passive"))
    )
    (net (code "103") (name "Net-(JP1-Pad18)") (class "Default")
      (node (ref "JP1") (pin "18") (pinfunction "18_18") (pintype "passive"))
      (node (ref "R20") (pin "1") (pinfunction "1_1") (pintype "passive"))
    )
    (net (code "104") (name "Net-(JP1-Pad20)") (class "Default")
      (node (ref "JP1") (pin "20") (pinfunction "20_20") (pintype "passive"))
      (node (ref "R21") (pin "1") (pinfunction "1_1") (pintype "passive"))
    )
    (net (code "105") (name "Net-(JP1-Pad22)") (class "Default")
      (node (ref "JP1") (pin "22") (pinfunction "22_22") (pintype "passive"))
      (node (ref "R22") (pin "1") (pinfunction "1_1") (pintype "passive"))
    )
    (net (code "106") (name "Net-(JP1-Pad24)") (class "Default")
      (node (ref "JP1") (pin "24") (pinfunction "24_24") (pintype "passive"))
      (node (ref "R23") (pin "1") (pinfunction "1_1") (pintype "passive"))
    )
    (net (code "107") (name "Net-(LED1-PadA)") (class "Default")
      (node (ref "LED1") (pin "A") (pinfunction "A_A") (pintype "passive"))
      (node (ref "RN1") (pin "1") (pinfunction "1_1") (pintype "passive"))
    )
    (net (code "108") (name "Net-(LED5-PadA)") (class "Default")
      (node (ref "LED5") (pin "A") (pinfunction "A_A") (pintype "passive"))
      (node (ref "R25") (pin "1") (pinfunction "1_1") (pintype "passive"))
    )
    (net (code "109") (name "Net-(LED6-PadA)") (class "Default")
      (node (ref "LED6") (pin "A") (pinfunction "A_A") (pintype "passive"))
      (node (ref "R44") (pin "1") (pinfunction "1_1") (pintype "passive"))
    )
    (net (code "110") (name "Net-(LED7-PadA)") (class "Default")
      (node (ref "LED7") (pin "A") (pinfunction "A_A") (pintype "passive"))
      (node (ref "R47") (pin "1") (pinfunction "1_1") (pintype "passive"))
    )
    (net (code "111") (name "Net-(LED8-PadC)") (class "Default")
      (node (ref "LED8") (pin "C") (pinfunction "C_C") (pintype "passive"))
      (node (ref "R60") (pin "2") (pinfunction "2_2") (pintype "passive"))
    )
    (net (code "112") (name "Net-(R4-Pad2)") (class "Default")
      (node (ref "R4") (pin "2") (pinfunction "2_2") (pintype "passive"))
      (node (ref "R5") (pin "2") (pinfunction "2_2") (pintype "passive"))
      (node (ref "X1") (pin "1") (pinfunction "1_1") (pintype "passive"))
    )
    (net (code "113") (name "Net-(R11-Pad1)") (class "Default")
      (node (ref "R11") (pin "1") (pinfunction "1_1") (pintype "passive"))
      (node (ref "R24") (pin "2") (pinfunction "2_2") (pintype "passive"))
      (node (ref "X2") (pin "1") (pinfunction "1_1") (pintype "passive"))
    )
    (net (code "114") (name "Net-(RN1B-1)") (class "Default")
      (node (ref "LED2") (pin "A") (pinfunction "A_A") (pintype "passive"))
      (node (ref "RN1") (pin "2") (pinfunction "1_2") (pintype "passive"))
    )
    (net (code "115") (name "Net-(RN1C-1)") (class "Default")
      (node (ref "LED3") (pin "A") (pinfunction "A_A") (pintype "passive"))
      (node (ref "RN1") (pin "3") (pinfunction "1_3") (pintype "passive"))
    )
    (net (code "116") (name "Net-(RN1D-1)") (class "Default")
      (node (ref "LED4") (pin "A") (pinfunction "A_A") (pintype "passive"))
      (node (ref "RN1") (pin "4") (pinfunction "1_4") (pintype "passive"))
    )
    (net (code "117") (name "Net-(T1-D)") (class "Default")
      (node (ref "LED6") (pin "C") (pinfunction "C_C") (pintype "passive"))
      (node (ref "T1") (pin "3") (pinfunction "D_3") (pintype "passive"))
    )
    (net (code "118") (name "Net-(T1-G)") (class "Default")
      (node (ref "R43") (pin "2") (pinfunction "2_2") (pintype "passive"))
      (node (ref "T1") (pin "1") (pinfunction "G_1") (pintype "passive"))
    )
    (net (code "119") (name "Net-(XO1-OUT)") (class "Default")
      (node (ref "R10") (pin "1") (pinfunction "1_1") (pintype "passive"))
      (node (ref "R12") (pin "2") (pinfunction "2_2") (pintype "passive"))
      (node (ref "XO1") (pin "3") (pinfunction "OUT_3") (pintype "output"))
    )
    (net (code "120") (name "PXCK_EXT") (class "Default")
      (node (ref "IC6") (pin "128") (pinfunction "IOT_84_GBIN1_128") (pintype "bidirectional"))
      (node (ref "R23") (pin "2") (pinfunction "2_2") (pintype "passive"))
    )
    (net (code "121") (name "RXD") (class "Default")
      (node (ref "CN6") (pin "3") (pinfunction "3_3") (pintype "bidirectional"))
      (node (ref "IC10") (pin "10") (pinfunction "PA05_10") (pintype "bidirectional"))
    )
    (net (code "122") (name "SCL") (class "Default")
      (node (ref "CN8") (pin "3") (pinfunction "3_3") (pintype "bidirectional"))
      (node (ref "IC10") (pin "32") (pinfunction "PA23_32") (pintype "bidirectional"))
      (node (ref "IC3") (pin "21") (pinfunction "SCL_21") (pintype "passive"))
      (node (ref "JP2") (pin "2") (pinfunction "2_2") (pintype "passive"))
      (node (ref "R49") (pin "2") (pinfunction "2_2") (pintype "passive"))
      (node (ref "R53") (pin "1") (pinfunction "1_1") (pintype "passive"))
      (node (ref "R54") (pin "2") (pinfunction "2_2") (pintype "passive"))
    )
    (net (code "123") (name "SD0") (class "Default")
      (node (ref "IC6") (pin "118") (pinfunction "IOT_79_118") (pintype "bidirectional"))
      (node (ref "R13") (pin "2") (pinfunction "2_2") (pintype "passive"))
    )
    (net (code "124") (name "SD1") (class "Default")
      (node (ref "IC6") (pin "119") (pinfunction "IOT_80_119") (pintype "bidirectional"))
      (node (ref "R14") (pin "2") (pinfunction "2_2") (pintype "passive"))
    )
    (net (code "125") (name "SD2") (class "Default")
      (node (ref "IC6") (pin "120") (pinfunction "IOT_81_120") (pintype "bidirectional"))
      (node (ref "R15") (pin "2") (pinfunction "2_2") (pintype "passive"))
    )
    (net (code "126") (name "SD3") (class "Default")
      (node (ref "IC6") (pin "121") (pinfunction "IOT_82_121") (pintype "bidirectional"))
      (node (ref "R16") (pin "2") (pinfunction "2_2") (pintype "passive"))
    )
    (net (code "127") (name "SD4") (class "Default")
      (node (ref "IC6") (pin "122") (pinfunction "IOT_83_122") (pintype "bidirectional"))
      (node (ref "R17") (pin "2") (pinfunction "2_2") (pintype "passive"))
    )
    (net (code "128") (name "SD5") (class "Default")
      (node (ref "IC6") (pin "134") (pinfunction "IOT_87_134") (pintype "bidirectional"))
      (node (ref "R18") (pin "2") (pinfunction "2_2") (pintype "passive"))
    )
    (net (code "129") (name "SD6") (class "Default")
      (node (ref "IC6") (pin "135") (pinfunction "IOT_88_135") (pintype "bidirectional"))
      (node (ref "R19") (pin "2") (pinfunction "2_2") (pintype "passive"))
    )
    (net (code "130") (name "SD7") (class "Default")
      (node (ref "IC6") (pin "136") (pinfunction "IOT_89_136") (pintype "bidirectional"))
      (node (ref "R20") (pin "2") (pinfunction "2_2") (pintype "passive"))
    )
    (net (code "131") (name "SD8") (class "Default")
      (node (ref "IC6") (pin "137") (pinfunction "IOT_90_137") (pintype "bidirectional"))
      (node (ref "R21") (pin "2") (pinfunction "2_2") (pintype "passive"))
    )
    (net (code "132") (name "SD9") (class "Default")
      (node (ref "IC6") (pin "138") (pinfunction "IOT_91_138") (pintype "bidirectional"))
      (node (ref "R22") (pin "2") (pinfunction "2_2") (pintype "passive"))
    )
    (net (code "133") (name "SDA") (class "Default")
      (node (ref "CN8") (pin "4") (pinfunction "4_4") (pintype "bidirectional"))
      (node (ref "IC10") (pin "31") (pinfunction "PA22_31") (pintype "bidirectional"))
      (node (ref "IC3") (pin "22") (pinfunction "SDA_22") (pintype "passive"))
      (node (ref "JP2") (pin "4") (pinfunction "4_4") (pintype "passive"))
      (node (ref "R48") (pin "2") (pinfunction "2_2") (pintype "passive"))
      (node (ref "R52") (pin "1") (pinfunction "1_1") (pintype "passive"))
      (node (ref "R55") (pin "2") (pinfunction "2_2") (pintype "passive"))
    )
    (net (code "134") (name "SDO_N") (class "Default")
      (node (ref "IC6") (pin "33") (pinfunction "IOL_12A_33") (pintype "bidirectional"))
      (node (ref "R3") (pin "1") (pinfunction "1_1") (pintype "passive"))
    )
    (net (code "135") (name "SDO_P") (class "Default")
      (node (ref "IC6") (pin "34") (pinfunction "IOL_12B_34") (pintype "bidirectional"))
      (node (ref "R2") (pin "1") (pinfunction "1_1") (pintype "passive"))
    )
    (net (code "136") (name "SERDES_CK_N") (class "Default")
      (node (ref "C6") (pin "1") (pinfunction "1_1") (pintype "passive"))
      (node (ref "IC6") (pin "24") (pinfunction "IOL_8B_24") (pintype "bidirectional"))
    )
    (net (code "137") (name "SERDES_CK_P") (class "Default")
      (node (ref "C3") (pin "1") (pinfunction "1_1") (pintype "passive"))
      (node (ref "IC6") (pin "23") (pinfunction "IOL_8A_23") (pintype "bidirectional"))
    )
    (net (code "138") (name "SRAM_A0") (class "Default")
      (node (ref "IC5") (pin "5") (pinfunction "A0_5") (pintype "input"))
      (node (ref "IC6") (pin "62") (pinfunction "IOB_41_62") (pintype "bidirectional"))
    )
    (net (code "139") (name "SRAM_A1") (class "Default")
      (node (ref "IC5") (pin "4") (pinfunction "A1_4") (pintype "input"))
      (node (ref "IC6") (pin "73") (pinfunction "IOR_48_73") (pintype "bidirectional"))
    )
    (net (code "140") (name "SRAM_A2") (class "Default")
      (node (ref "IC5") (pin "3") (pinfunction "A2_3") (pintype "input"))
      (node (ref "IC6") (pin "74") (pinfunction "IOR_49_74") (pintype "bidirectional"))
    )
    (net (code "141") (name "SRAM_A3") (class "Default")
      (node (ref "IC5") (pin "2") (pinfunction "A3_2") (pintype "input"))
      (node (ref "IC6") (pin "75") (pinfunction "IOR_50_75") (pintype "bidirectional"))
    )
    (net (code "142") (name "SRAM_A4") (class "Default")
      (node (ref "IC5") (pin "1") (pinfunction "A4_1") (pintype "input"))
      (node (ref "IC6") (pin "76") (pinfunction "IOR_51_76") (pintype "bidirectional"))
    )
    (net (code "143") (name "SRAM_A5") (class "Default")
      (node (ref "IC5") (pin "44") (pinfunction "A5_44") (pintype "input"))
      (node (ref "IC6") (pin "99") (pinfunction "IOR_66_99") (pintype "bidirectional"))
    )
    (net (code "144") (name "SRAM_A6") (class "Default")
      (node (ref "IC5") (pin "43") (pinfunction "A6_43") (pintype "input"))
      (node (ref "IC6") (pin "101") (pinfunction "IOR_67_101") (pintype "bidirectional"))
    )
    (net (code "145") (name "SRAM_A7") (class "Default")
      (node (ref "IC5") (pin "42") (pinfunction "A7_42") (pintype "input"))
      (node (ref "IC6") (pin "102") (pinfunction "IOR_68_102") (pintype "bidirectional"))
    )
    (net (code "146") (name "SRAM_A8") (class "Default")
      (node (ref "IC5") (pin "28") (pinfunction "A8_28") (pintype "input"))
      (node (ref "IC6") (pin "81") (pinfunction "IOR_55_81") (pintype "bidirectional"))
    )
    (net (code "147") (name "SRAM_A9") (class "Default")
      (node (ref "IC5") (pin "27") (pinfunction "A9_27") (pintype "input"))
      (node (ref "IC6") (pin "80") (pinfunction "IOR_54_80") (pintype "bidirectional"))
    )
    (net (code "148") (name "SRAM_A10") (class "Default")
      (node (ref "IC5") (pin "26") (pinfunction "A10_26") (pintype "input"))
      (node (ref "IC6") (pin "79") (pinfunction "IOR_53_79") (pintype "bidirectional"))
    )
    (net (code "149") (name "SRAM_A11") (class "Default")
      (node (ref "IC5") (pin "25") (pinfunction "A11_25") (pintype "input"))
      (node (ref "IC6") (pin "39") (pinfunction "IOB_26_39") (pintype "bidirectional"))
    )
    (net (code "150") (name "SRAM_A12") (class "Default")
      (node (ref "IC5") (pin "24") (pinfunction "A12_24") (pintype "input"))
      (node (ref "IC6") (pin "38") (pinfunction "IOB_25_38") (pintype "bidirectional"))
    )
    (net (code "151") (name "SRAM_A13") (class "Default")
      (node (ref "IC5") (pin "23") (pinfunction "A13_23") (pintype "input"))
      (node (ref "IC6") (pin "37") (pinfunction "IOB_24_37") (pintype "bidirectional"))
    )
    (net (code "152") (name "SRAM_A14") (class "Default")
      (node (ref "IC5") (pin "22") (pinfunction "A14_22") (pintype "input"))
      (node (ref "IC6") (pin "41") (pinfunction "IOB_27_41") (pintype "bidirectional"))
    )
    (net (code "153") (name "SRAM_A15") (class "Default")
      (node (ref "IC5") (pin "21") (pinfunction "A15_21") (pintype "input"))
      (node (ref "IC6") (pin "42") (pinfunction "IOB_28_42") (pintype "bidirectional"))
    )
    (net (code "154") (name "SRAM_A16") (class "Default")
      (node (ref "IC5") (pin "20") (pinfunction "A16_20") (pintype "input"))
      (node (ref "IC6") (pin "43") (pinfunction "IOB_29_43") (pintype "bidirectional"))
    )
    (net (code "155") (name "SRAM_A17") (class "Default")
      (node (ref "IC5") (pin "19") (pinfunction "A17_19") (pintype "input"))
      (node (ref "IC6") (pin "44") (pinfunction "IOB_30_44") (pintype "bidirectional"))
    )
    (net (code "156") (name "SRAM_A18") (class "Default")
      (node (ref "IC5") (pin "18") (pinfunction "A18_18") (pintype "input"))
      (node (ref "IC6") (pin "45") (pinfunction "IOB_31_45") (pintype "bidirectional"))
    )
    (net (code "157") (name "SRAM_D0") (class "Default")
      (node (ref "IC5") (pin "7") (pinfunction "I/O0_7") (pintype "bidirectional"))
      (node (ref "IC6") (pin "61") (pinfunction "IOB_40_61") (pintype "bidirectional"))
    )
    (net (code "158") (name "SRAM_D1") (class "Default")
      (node (ref "IC5") (pin "8") (pinfunction "I/O1_8") (pintype "bidirectional"))
      (node (ref "IC6") (pin "60") (pinfunction "IOB_39_60") (pintype "bidirectional"))
    )
    (net (code "159") (name "SRAM_D2") (class "Default")
      (node (ref "IC5") (pin "9") (pinfunction "I/O2_9") (pintype "bidirectional"))
      (node (ref "IC6") (pin "58") (pinfunction "IOB_38_58") (pintype "bidirectional"))
    )
    (net (code "160") (name "SRAM_D3") (class "Default")
      (node (ref "IC5") (pin "10") (pinfunction "I/O3_10") (pintype "bidirectional"))
      (node (ref "IC6") (pin "56") (pinfunction "IOB_37_56") (pintype "bidirectional"))
    )
    (net (code "161") (name "SRAM_D4") (class "Default")
      (node (ref "IC5") (pin "13") (pinfunction "I/O4_13") (pintype "bidirectional"))
      (node (ref "IC6") (pin "52") (pinfunction "IOB_34_52") (pintype "bidirectional"))
    )
    (net (code "162") (name "SRAM_D5") (class "Default")
      (node (ref "IC5") (pin "14") (pinfunction "I/O5_14") (pintype "bidirectional"))
      (node (ref "IC6") (pin "50") (pinfunction "IOB_36_GBIN4_50") (pintype "bidirectional"))
    )
    (net (code "163") (name "SRAM_D6") (class "Default")
      (node (ref "IC5") (pin "15") (pinfunction "I/O6_15") (pintype "bidirectional"))
      (node (ref "IC6") (pin "49") (pinfunction "IOB_35_GBIN5_49") (pintype "bidirectional"))
    )
    (net (code "164") (name "SRAM_D7") (class "Default")
      (node (ref "IC5") (pin "16") (pinfunction "I/O7_16") (pintype "bidirectional"))
      (node (ref "IC6") (pin "48") (pinfunction "IOB_33_48") (pintype "bidirectional"))
    )
    (net (code "165") (name "SRAM_D8") (class "Default")
      (node (ref "IC5") (pin "29") (pinfunction "I/O8_29") (pintype "bidirectional"))
      (node (ref "IC6") (pin "87") (pinfunction "IOR_56_87") (pintype "bidirectional"))
    )
    (net (code "166") (name "SRAM_D9") (class "Default")
      (node (ref "IC5") (pin "30") (pinfunction "I/O9_30") (pintype "bidirectional"))
      (node (ref "IC6") (pin "88") (pinfunction "IOR_57_88") (pintype "bidirectional"))
    )
    (net (code "167") (name "SRAM_D10") (class "Default")
      (node (ref "IC5") (pin "31") (pinfunction "I/O10_31") (pintype "bidirectional"))
      (node (ref "IC6") (pin "90") (pinfunction "IOR_58_90") (pintype "bidirectional"))
    )
    (net (code "168") (name "SRAM_D11") (class "Default")
      (node (ref "IC5") (pin "32") (pinfunction "I/O11_32") (pintype "bidirectional"))
      (node (ref "IC6") (pin "91") (pinfunction "IOR_59_91") (pintype "bidirectional"))
    )
    (net (code "169") (name "SRAM_D12") (class "Default")
      (node (ref "IC5") (pin "35") (pinfunction "I/O12_35") (pintype "bidirectional"))
      (node (ref "IC6") (pin "93") (pinfunction "IOR_60_GBIN3_93") (pintype "bidirectional"))
    )
    (net (code "170") (name "SRAM_D13") (class "Default")
      (node (ref "IC5") (pin "36") (pinfunction "I/O13_36") (pintype "bidirectional"))
      (node (ref "IC6") (pin "94") (pinfunction "IOR_61_GBIN2_94") (pintype "bidirectional"))
    )
    (net (code "171") (name "SRAM_D14") (class "Default")
      (node (ref "IC5") (pin "37") (pinfunction "I/O14_37") (pintype "bidirectional"))
      (node (ref "IC6") (pin "95") (pinfunction "IOR_62_95") (pintype "bidirectional"))
    )
    (net (code "172") (name "SRAM_D15") (class "Default")
      (node (ref "IC5") (pin "38") (pinfunction "I/O15_38") (pintype "bidirectional"))
      (node (ref "IC6") (pin "96") (pinfunction "IOR_63_96") (pintype "bidirectional"))
    )
    (net (code "173") (name "SWDCLK") (class "Default")
      (node (ref "IC10") (pin "45") (pinfunction "PA30_45") (pintype "bidirectional"))
      (node (ref "JP3") (pin "4") (pinfunction "4_4") (pintype "passive"))
    )
    (net (code "174") (name "SWDIO") (class "Default")
      (node (ref "IC10") (pin "46") (pinfunction "PA31_46") (pintype "bidirectional"))
      (node (ref "JP3") (pin "2") (pinfunction "2_2") (pintype "passive"))
    )
    (net (code "175") (name "TVP_CLK") (class "Default")
      (node (ref "IC6") (pin "97") (pinfunction "IOR_64_97") (pintype "bidirectional"))
      (node (ref "R26") (pin "2") (pinfunction "2_2") (pintype "passive"))
    )
    (net (code "176") (name "TVP_D0") (class "Default")
      (node (ref "IC6") (pin "106") (pinfunction "IOR_71_106") (pintype "bidirectional"))
      (node (ref "RN3") (pin "8") (pinfunction "B1_8") (pintype "passive"))
    )
    (net (code "177") (name "TVP_D1") (class "Default")
      (node (ref "IC6") (pin "107") (pinfunction "IOR_72_107") (pintype "bidirectional"))
      (node (ref "RN3") (pin "7") (pinfunction "B2_7") (pintype "passive"))
    )
    (net (code "178") (name "TVP_D2") (class "Default")
      (node (ref "IC6") (pin "112") (pinfunction "IOT_73_112") (pintype "bidirectional"))
      (node (ref "RN3") (pin "6") (pinfunction "B3_6") (pintype "passive"))
    )
    (net (code "179") (name "TVP_D3") (class "Default")
      (node (ref "IC6") (pin "113") (pinfunction "IOT_74_113") (pintype "bidirectional"))
      (node (ref "RN3") (pin "5") (pinfunction "B4_5") (pintype "passive"))
    )
    (net (code "180") (name "TVP_D4") (class "Default")
      (node (ref "IC6") (pin "114") (pinfunction "IOT_75_114") (pintype "bidirectional"))
      (node (ref "RN4") (pin "8") (pinfunction "B1_8") (pintype "passive"))
    )
    (net (code "181") (name "TVP_D5") (class "Default")
      (node (ref "IC6") (pin "115") (pinfunction "IOT_76_115") (pintype "bidirectional"))
      (node (ref "RN4") (pin "7") (pinfunction "B2_7") (pintype "passive"))
    )
    (net (code "182") (name "TVP_D6") (class "Default")
      (node (ref "IC6") (pin "116") (pinfunction "IOT_77_116") (pintype "bidirectional"))
      (node (ref "RN4") (pin "6") (pinfunction "B3_6") (pintype "passive"))
    )
    (net (code "183") (name "TVP_D7") (class "Default")
      (node (ref "IC6") (pin "117") (pinfunction "IOT_78_117") (pintype "bidirectional"))
      (node (ref "RN4") (pin "5") (pinfunction "B4_5") (pintype "passive"))
    )
    (net (code "184") (name "TXD") (class "Default")
      (node (ref "CN6") (pin "2") (pinfunction "2_2") (pintype "bidirectional"))
      (node (ref "IC10") (pin "9") (pinfunction "PA04_9") (pintype "bidirectional"))
    )
    (net (code "185") (name "USBD_N") (class "Default")
      (node (ref "CN5") (pin "2") (pinfunction "D-_2") (pintype "bidirectional"))
      (node (ref "IC10") (pin "33") (pinfunction "PA24_33") (pintype "bidirectional"))
    )
    (net (code "186") (name "USBD_P") (class "Default")
      (node (ref "CN5") (pin "3") (pinfunction "D+_3") (pintype "bidirectional"))
      (node (ref "IC10") (pin "34") (pinfunction "PA25_34") (pintype "bidirectional"))
    )
    (net (code "187") (name "V+") (class "Default")
      (node (ref "C59") (pin "1") (pinfunction "1_1") (pintype "passive"))
      (node (ref "C66") (pin "+") (pinfunction "+_+") (pintype "passive"))
      (node (ref "CN7") (pin "1") (pinfunction "1_1") (pintype "bidirectional"))
      (node (ref "D2") (pin "C") (pinfunction "C_C") (pintype "passive"))
      (node (ref "IC9") (pin "3") (pinfunction "VIN_3") (pintype "power_in"))
      (node (ref "IC9") (pin "5") (pinfunction "EN_5") (pintype "input"))
    )
    (net (code "188") (name "VCORE") (class "Default")
      (node (ref "C319") (pin "1") (pinfunction "1_1") (pintype "passive"))
      (node (ref "C35") (pin "1") (pinfunction "1_1") (pintype "passive"))
      (node (ref "C36") (pin "1") (pinfunction "1_1") (pintype "passive"))
      (node (ref "C37") (pin "1") (pinfunction "1_1") (pintype "passive"))
      (node (ref "C38") (pin "1") (pinfunction "1_1") (pintype "passive"))
      (node (ref "C65") (pin "+") (pinfunction "+_+") (pintype "passive"))
      (node (ref "IC305") (pin "5") (pinfunction "VOUT_5") (pintype "passive"))
      (node (ref "IC6") (pin "111") (pinfunction "VCC_111") (pintype "power_in"))
      (node (ref "IC6") (pin "27") (pinfunction "VCC_27") (pintype "power_in"))
      (node (ref "IC6") (pin "51") (pinfunction "VCC_51") (pintype "power_in"))
      (node (ref "IC6") (pin "92") (pinfunction "VCC_92") (pintype "power_in"))
      (node (ref "R37") (pin "1") (pinfunction "1_1") (pintype "passive"))
    )
    (net (code "189") (name "VPP_FAST") (class "Default")
      (node (ref "IC6") (pin "109") (pinfunction "VPP_FAST_109") (pintype "power_in"))
    )
    (net (code "190") (name "unconnected-(CN5-ID-Pad4)") (class "Default")
      (node (ref "CN5") (pin "4") (pinfunction "ID_4") (pintype "bidirectional"))
    )
    (net (code "191") (name "unconnected-(IC1-BPOUT-Pad13)") (class "Default")
      (node (ref "IC1") (pin "13") (pinfunction "BPOUT_13") (pintype "output"))
    )
    (net (code "192") (name "unconnected-(IC1-CSOUT-Pad12)") (class "Default")
      (node (ref "IC1") (pin "12") (pinfunction "CSOUT_12") (pintype "output"))
    )
    (net (code "193") (name "unconnected-(IC2-LFOUT-Pad15)") (class "Default")
      (node (ref "IC2") (pin "15") (pinfunction "LFOUT_15") (pintype "output"))
    )
    (net (code "194") (name "unconnected-(IC3A-FID{slash}GLCO-Pad23)") (class "Default")
      (node (ref "IC3") (pin "23") (pinfunction "FID/GLCO_23") (pintype "output"))
    )
    (net (code "195") (name "unconnected-(IC3A-HS-Pad25)") (class "Default")
      (node (ref "IC3") (pin "25") (pinfunction "HS_25") (pintype "output"))
    )
    (net (code "196") (name "unconnected-(IC3A-VS{slash}PALI-Pad24)") (class "Default")
      (node (ref "IC3") (pin "24") (pinfunction "VS/PALI_24") (pintype "output"))
    )
    (net (code "197") (name "unconnected-(IC6E-IOL_3A-Pad7)") (class "Default")
      (node (ref "IC6") (pin "7") (pinfunction "IOL_3A_7") (pintype "bidirectional"))
    )
    (net (code "198") (name "unconnected-(IC6E-IOL_3B-Pad8)") (class "Default")
      (node (ref "IC6") (pin "8") (pinfunction "IOL_3B_8") (pintype "bidirectional"))
    )
    (net (code "199") (name "unconnected-(IC6E-IOL_7A_GBIN6-Pad21)") (class "Default")
      (node (ref "IC6") (pin "21") (pinfunction "IOL_7A_GBIN6_21") (pintype "bidirectional"))
    )
    (net (code "200") (name "unconnected-(IC6E-IOL_7B-Pad22)") (class "Default")
      (node (ref "IC6") (pin "22") (pinfunction "IOL_7B_22") (pintype "bidirectional"))
    )
    (net (code "201") (name "unconnected-(IC6E-IOL_9A-Pad25)") (class "Default")
      (node (ref "IC6") (pin "25") (pinfunction "IOL_9A_25") (pintype "bidirectional"))
    )
    (net (code "202") (name "unconnected-(IC6E-IOL_9B-Pad26)") (class "Default")
      (node (ref "IC6") (pin "26") (pinfunction "IOL_9B_26") (pintype "bidirectional"))
    )
    (net (code "203") (name "unconnected-(IC6E-IOL_10A-Pad28)") (class "Default")
      (node (ref "IC6") (pin "28") (pinfunction "IOL_10A_28") (pintype "bidirectional"))
    )
    (net (code "204") (name "unconnected-(IC6E-IOL_10B-Pad29)") (class "Default")
      (node (ref "IC6") (pin "29") (pinfunction "IOL_10B_29") (pintype "bidirectional"))
    )
    (net (code "205") (name "unconnected-(IC6E-IOL_11A-Pad31)") (class "Default")
      (node (ref "IC6") (pin "31") (pinfunction "IOL_11A_31") (pintype "bidirectional"))
    )
    (net (code "206") (name "unconnected-(IC6E-IOL_11B-Pad32)") (class "Default")
      (node (ref "IC6") (pin "32") (pinfunction "IOL_11B_32") (pintype "bidirectional"))
    )
    (net (code "207") (name "unconnected-(IC10A-PA06-Pad11)") (class "Default")
      (node (ref "IC10") (pin "11") (pinfunction "PA06_11") (pintype "bidirectional"))
    )
    (net (code "208") (name "unconnected-(IC10A-PA07-Pad12)") (class "Default")
      (node (ref "IC10") (pin "12") (pinfunction "PA07_12") (pintype "bidirectional"))
    )
    (net (code "209") (name "unconnected-(IC10A-PA08-Pad13)") (class "Default")
      (node (ref "IC10") (pin "13") (pinfunction "PA08_13") (pintype "bidirectional"))
    )
    (net (code "210") (name "unconnected-(IC10A-PA12-Pad21)") (class "Default")
      (node (ref "IC10") (pin "21") (pinfunction "PA12_21") (pintype "bidirectional"))
    )
    (net (code "211") (name "unconnected-(IC10A-PA13-Pad22)") (class "Default")
      (node (ref "IC10") (pin "22") (pinfunction "PA13_22") (pintype "bidirectional"))
    )
    (net (code "212") (name "unconnected-(IC10A-PA18-Pad27)") (class "Default")
      (node (ref "IC10") (pin "27") (pinfunction "PA18_27") (pintype "bidirectional"))
    )
    (net (code "213") (name "unconnected-(IC10A-PA19-Pad28)") (class "Default")
      (node (ref "IC10") (pin "28") (pinfunction "PA19_28") (pintype "bidirectional"))
    )
    (net (code "214") (name "unconnected-(IC10A-PA20-Pad29)") (class "Default")
      (node (ref "IC10") (pin "29") (pinfunction "PA20_29") (pintype "bidirectional"))
    )
    (net (code "215") (name "unconnected-(IC10A-PA27-Pad39)") (class "Default")
      (node (ref "IC10") (pin "39") (pinfunction "PA27_39") (pintype "bidirectional"))
    )
    (net (code "216") (name "unconnected-(IC10A-PA28-Pad41)") (class "Default")
      (node (ref "IC10") (pin "41") (pinfunction "PA28_41") (pintype "bidirectional"))
    )
    (net (code "217") (name "unconnected-(IC10A-PB02-Pad47)") (class "Default")
      (node (ref "IC10") (pin "47") (pinfunction "PB02_47") (pintype "bidirectional"))
    )
    (net (code "218") (name "unconnected-(IC10A-PB03-Pad48)") (class "Default")
      (node (ref "IC10") (pin "48") (pinfunction "PB03_48") (pintype "bidirectional"))
    )
    (net (code "219") (name "unconnected-(IC10A-PB10-Pad19)") (class "Default")
      (node (ref "IC10") (pin "19") (pinfunction "PB10_19") (pintype "bidirectional"))
    )
    (net (code "220") (name "unconnected-(IC10A-PB11-Pad20)") (class "Default")
      (node (ref "IC10") (pin "20") (pinfunction "PB11_20") (pintype "bidirectional"))
    )
    (net (code "221") (name "unconnected-(IC305-FB{slash}NC-Pad4)") (class "Default")
      (node (ref "IC305") (pin "4") (pinfunction "FB/NC_4") (pintype "passive"))
    )
    (net (code "222") (name "unconnected-(JP3-Pad6)") (class "Default")
      (node (ref "JP3") (pin "6") (pinfunction "6_6") (pintype "passive"))
    )
    (net (code "223") (name "unconnected-(JP3-Pad7)") (class "Default")
      (node (ref "JP3") (pin "7") (pinfunction "7_7") (pintype "passive"))
    )
    (net (code "224") (name "unconnected-(JP3-Pad8)") (class "Default")
      (node (ref "JP3") (pin "8") (pinfunction "8_8") (pintype "passive"))
    )
    (net (code "225") (name "unconnected-(SW1-S1-Pad4)") (class "Default")
      (node (ref "SW1") (pin "4") (pinfunction "S1_4") (pintype "passive"))
    )
    (net (code "226") (name "~{CFG_CS}") (class "Default")
      (node (ref "IC8") (pin "1") (pinfunction "~{SS}_1") (pintype "bidirectional"))
      (node (ref "R35") (pin "1") (pinfunction "1_1") (pintype "passive"))
      (node (ref "RN5") (pin "5") (pinfunction "B4_5") (pintype "passive"))
      (node (ref "RN6") (pin "4") (pinfunction "A4_4") (pintype "passive"))
    )
    (net (code "227") (name "~{FLASH_CS}") (class "Default")
      (node (ref "IC10") (pin "37") (pinfunction "PB22_37") (pintype "bidirectional"))
      (node (ref "JP2") (pin "10") (pinfunction "10_10") (pintype "passive"))
      (node (ref "RN6") (pin "5") (pinfunction "B4_5") (pintype "passive"))
    )
    (net (code "228") (name "~{FPGA_CRST}") (class "Default")
      (node (ref "IC10") (pin "38") (pinfunction "PB23_38") (pintype "bidirectional"))
      (node (ref "IC6") (pin "66") (pinfunction "CRESET_B_66") (pintype "bidirectional"))
      (node (ref "JP2") (pin "3") (pinfunction "3_3") (pintype "passive"))
      (node (ref "R56") (pin "2") (pinfunction "2_2") (pintype "passive"))
      (node (ref "R59") (pin "1") (pinfunction "1_1") (pintype "passive"))
    )
    (net (code "229") (name "~{MCU_RST}") (class "Default")
      (node (ref "IC10") (pin "40") (pinfunction "~{RESET}_40") (pintype "passive"))
      (node (ref "JP2") (pin "11") (pinfunction "11_11") (pintype "passive"))
      (node (ref "JP3") (pin "10") (pinfunction "10_10") (pintype "passive"))
      (node (ref "R46") (pin "1") (pinfunction "1_1") (pintype "passive"))
      (node (ref "SW1") (pin "3") (pinfunction "S_3") (pintype "passive"))
    )
    (net (code "230") (name "~{SRAM_CS}") (class "Default")
      (node (ref "IC5") (pin "6") (pinfunction "~{CS}_6") (pintype "input"))
      (node (ref "IC6") (pin "78") (pinfunction "IOR_52_78") (pintype "bidirectional"))
    )
    (net (code "231") (name "~{SRAM_LB}") (class "Default")
      (node (ref "IC5") (pin "39") (pinfunction "~{LB}_39") (pintype "input"))
      (node (ref "IC6") (pin "98") (pinfunction "IOR_65_98") (pintype "bidirectional"))
    )
    (net (code "232") (name "~{SRAM_OE}") (class "Default")
      (node (ref "IC5") (pin "41") (pinfunction "~{OE}_41") (pintype "input"))
      (node (ref "IC6") (pin "104") (pinfunction "IOR_69_104") (pintype "bidirectional"))
    )
    (net (code "233") (name "~{SRAM_UB}") (class "Default")
      (node (ref "IC5") (pin "40") (pinfunction "~{UB}_40") (pintype "input"))
      (node (ref "IC6") (pin "105") (pinfunction "IOR_70_105") (pintype "bidirectional"))
    )
    (net (code "234") (name "~{SRAM_WE}") (class "Default")
      (node (ref "IC5") (pin "17") (pinfunction "~{WE}_17") (pintype "input"))
      (node (ref "IC6") (pin "47") (pinfunction "IOB_32_47") (pintype "bidirectional"))
    )
    (net (code "235") (name "~{TVP_RST}") (class "Default")
      (node (ref "IC3") (pin "8") (pinfunction "~{RESET}_8") (pintype "passive"))
      (node (ref "R27") (pin "1") (pinfunction "1_1") (pintype "passive"))
    )
  )
)
